# Smart_Light_Panel.net
KiCad netlist of a schematic drawn in EAGLE
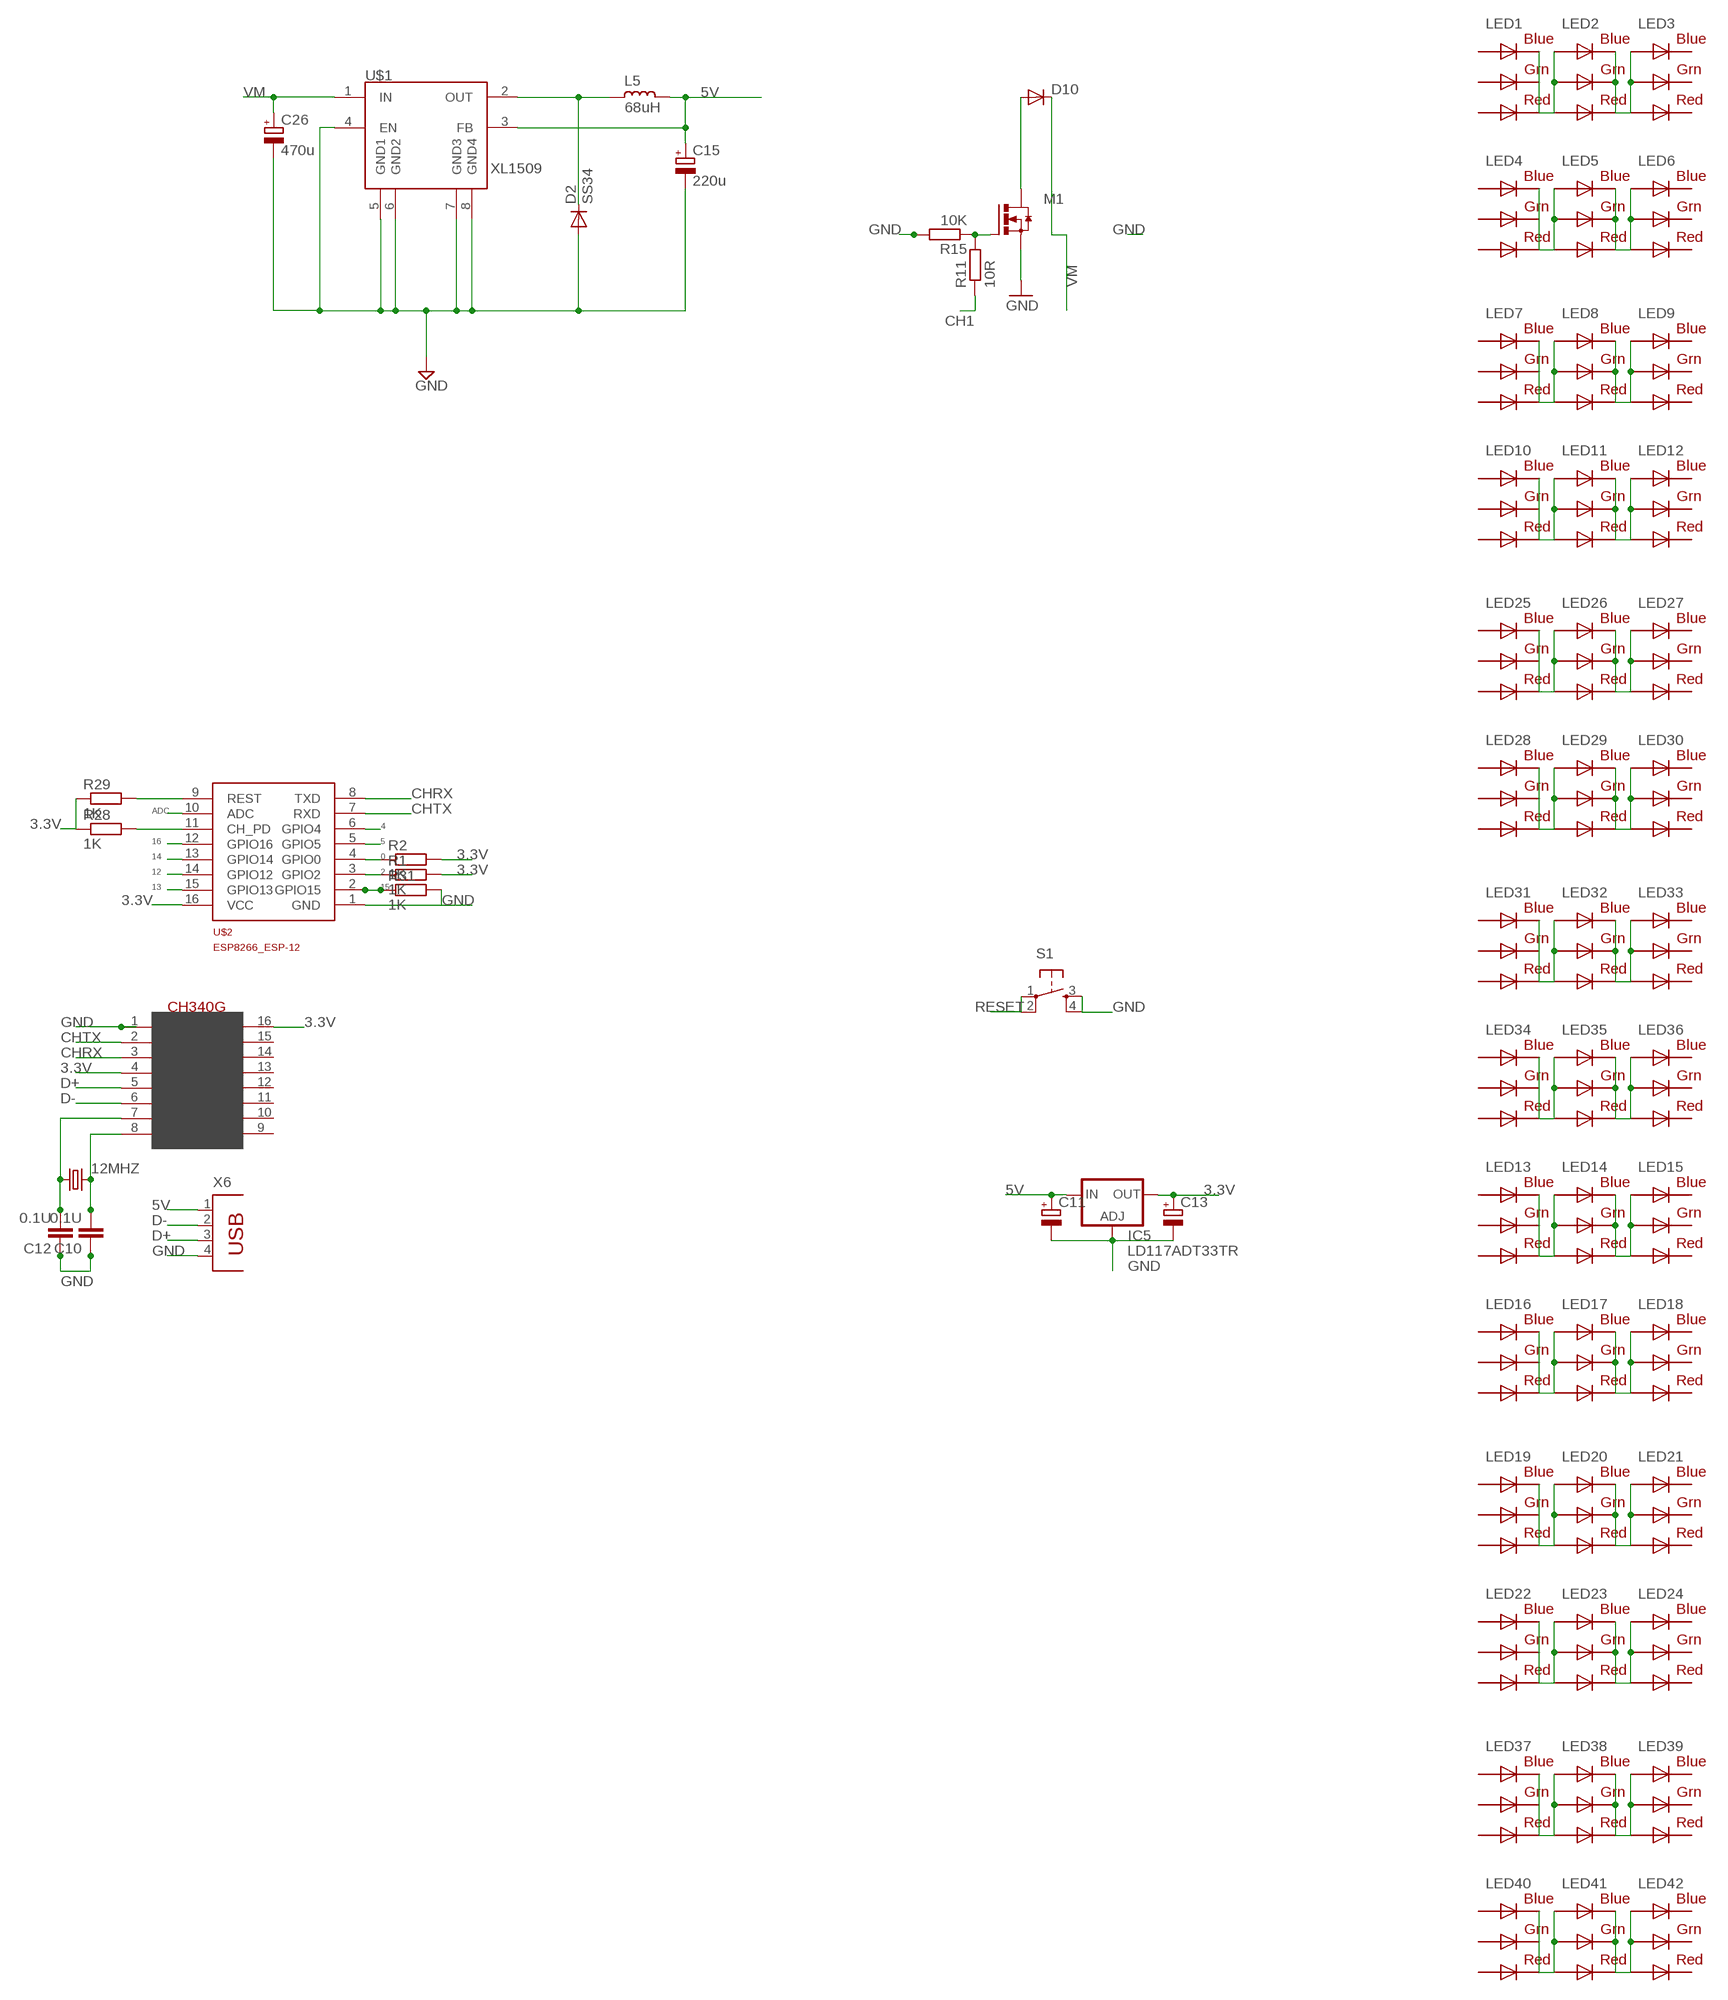
[diagram p0: schematic, sheet 1, part 1 of 2]
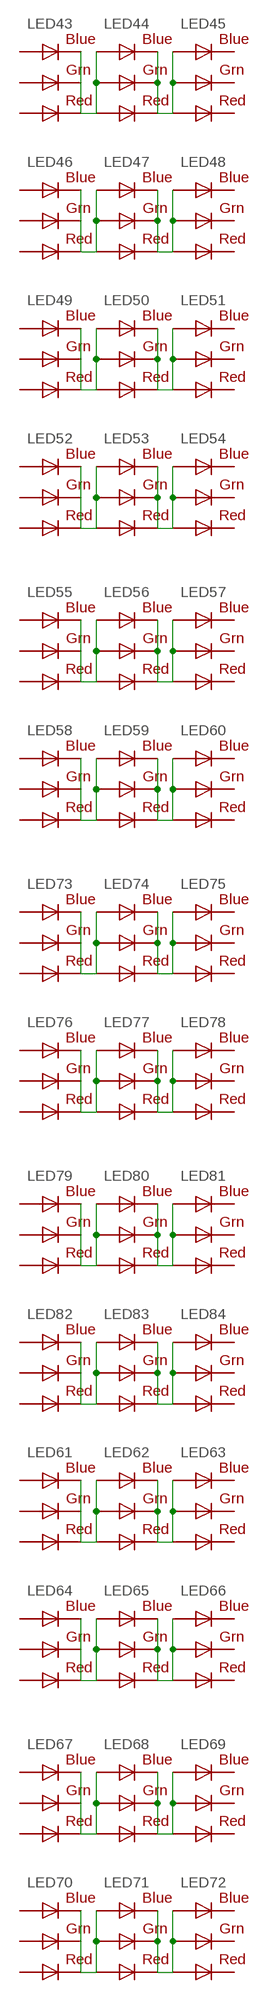
[diagram p1: schematic, sheet 1, part 2 of 2]

(export (version "E")
  (design (tool "Eeschema 10.0.6"))
  (components
    (comp (ref "12MHZ")
      (value "CRYSTALHC49UP")
      (footprint "eagle-import:HC49UP")
      (libsource (lib "eagle-import") (part "CRYSTALHC49UP"))
    )
    (comp (ref "C10")
      (value "0.1U")
      (footprint "eagle-import:C1206")
      (libsource (lib "eagle-import") (part "C-EUC1206"))
    )
    (comp (ref "C11")
      (value "CPOL-EUC")
      (footprint "eagle-import:PANASONIC_C")
      (libsource (lib "eagle-import") (part "CPOL-EUC"))
    )
    (comp (ref "C12")
      (value "0.1U")
      (footprint "eagle-import:C1206")
      (libsource (lib "eagle-import") (part "C-EUC1206"))
    )
    (comp (ref "C13")
      (value "CPOL-EUC")
      (footprint "eagle-import:PANASONIC_C")
      (libsource (lib "eagle-import") (part "CPOL-EUC"))
    )
    (comp (ref "C15")
      (value "220u")
      (footprint "eagle-import:E2,5-7")
      (libsource (lib "eagle-import") (part "CPOL-EUE2.5-7"))
    )
    (comp (ref "C26")
      (value "470u")
      (footprint "eagle-import:E2,5-7")
      (libsource (lib "eagle-import") (part "CPOL-EUE2.5-7"))
    )
    (comp (ref "D2")
      (value "SS34")
      (footprint "eagle-import:DO-214AC")
      (libsource (lib "eagle-import") (part "DIODE-DO-214AC"))
    )
    (comp (ref "D10")
      (value "DIODESMA-ALT")
      (footprint "eagle-import:SMA-DIODE_ALT")
      (libsource (lib "eagle-import") (part "DIODESMA-ALT"))
    )
    (comp (ref "IC5")
      (value "LD117ADT33TR")
      (footprint "eagle-import:DPACK")
      (libsource (lib "eagle-import") (part "LD117A?DT33TR"))
    )
    (comp (ref "L5")
      (value "68uH")
      (footprint "eagle-import:CD75")
      (libsource (lib "eagle-import") (part "L_CD75"))
    )
    (comp (ref "LED1")
      (value "RGBLED5050")
      (footprint "eagle-import:RGBLED5050")
      (libsource (lib "eagle-import") (part "RGBLED5050"))
    )
    (comp (ref "LED2")
      (value "RGBLED5050")
      (footprint "eagle-import:RGBLED5050")
      (libsource (lib "eagle-import") (part "RGBLED5050"))
    )
    (comp (ref "LED3")
      (value "RGBLED5050")
      (footprint "eagle-import:RGBLED5050")
      (libsource (lib "eagle-import") (part "RGBLED5050"))
    )
    (comp (ref "LED4")
      (value "RGBLED5050")
      (footprint "eagle-import:RGBLED5050")
      (libsource (lib "eagle-import") (part "RGBLED5050"))
    )
    (comp (ref "LED5")
      (value "RGBLED5050")
      (footprint "eagle-import:RGBLED5050")
      (libsource (lib "eagle-import") (part "RGBLED5050"))
    )
    (comp (ref "LED6")
      (value "RGBLED5050")
      (footprint "eagle-import:RGBLED5050")
      (libsource (lib "eagle-import") (part "RGBLED5050"))
    )
    (comp (ref "LED7")
      (value "RGBLED5050")
      (footprint "eagle-import:RGBLED5050")
      (libsource (lib "eagle-import") (part "RGBLED5050"))
    )
    (comp (ref "LED8")
      (value "RGBLED5050")
      (footprint "eagle-import:RGBLED5050")
      (libsource (lib "eagle-import") (part "RGBLED5050"))
    )
    (comp (ref "LED9")
      (value "RGBLED5050")
      (footprint "eagle-import:RGBLED5050")
      (libsource (lib "eagle-import") (part "RGBLED5050"))
    )
    (comp (ref "LED10")
      (value "RGBLED5050")
      (footprint "eagle-import:RGBLED5050")
      (libsource (lib "eagle-import") (part "RGBLED5050"))
    )
    (comp (ref "LED11")
      (value "RGBLED5050")
      (footprint "eagle-import:RGBLED5050")
      (libsource (lib "eagle-import") (part "RGBLED5050"))
    )
    (comp (ref "LED12")
      (value "RGBLED5050")
      (footprint "eagle-import:RGBLED5050")
      (libsource (lib "eagle-import") (part "RGBLED5050"))
    )
    (comp (ref "LED13")
      (value "RGBLED5050")
      (footprint "eagle-import:RGBLED5050")
      (libsource (lib "eagle-import") (part "RGBLED5050"))
    )
    (comp (ref "LED14")
      (value "RGBLED5050")
      (footprint "eagle-import:RGBLED5050")
      (libsource (lib "eagle-import") (part "RGBLED5050"))
    )
    (comp (ref "LED15")
      (value "RGBLED5050")
      (footprint "eagle-import:RGBLED5050")
      (libsource (lib "eagle-import") (part "RGBLED5050"))
    )
    (comp (ref "LED16")
      (value "RGBLED5050")
      (footprint "eagle-import:RGBLED5050")
      (libsource (lib "eagle-import") (part "RGBLED5050"))
    )
    (comp (ref "LED17")
      (value "RGBLED5050")
      (footprint "eagle-import:RGBLED5050")
      (libsource (lib "eagle-import") (part "RGBLED5050"))
    )
    (comp (ref "LED18")
      (value "RGBLED5050")
      (footprint "eagle-import:RGBLED5050")
      (libsource (lib "eagle-import") (part "RGBLED5050"))
    )
    (comp (ref "LED19")
      (value "RGBLED5050")
      (footprint "eagle-import:RGBLED5050")
      (libsource (lib "eagle-import") (part "RGBLED5050"))
    )
    (comp (ref "LED20")
      (value "RGBLED5050")
      (footprint "eagle-import:RGBLED5050")
      (libsource (lib "eagle-import") (part "RGBLED5050"))
    )
    (comp (ref "LED21")
      (value "RGBLED5050")
      (footprint "eagle-import:RGBLED5050")
      (libsource (lib "eagle-import") (part "RGBLED5050"))
    )
    (comp (ref "LED22")
      (value "RGBLED5050")
      (footprint "eagle-import:RGBLED5050")
      (libsource (lib "eagle-import") (part "RGBLED5050"))
    )
    (comp (ref "LED23")
      (value "RGBLED5050")
      (footprint "eagle-import:RGBLED5050")
      (libsource (lib "eagle-import") (part "RGBLED5050"))
    )
    (comp (ref "LED24")
      (value "RGBLED5050")
      (footprint "eagle-import:RGBLED5050")
      (libsource (lib "eagle-import") (part "RGBLED5050"))
    )
    (comp (ref "LED25")
      (value "RGBLED5050")
      (footprint "eagle-import:RGBLED5050")
      (libsource (lib "eagle-import") (part "RGBLED5050"))
    )
    (comp (ref "LED26")
      (value "RGBLED5050")
      (footprint "eagle-import:RGBLED5050")
      (libsource (lib "eagle-import") (part "RGBLED5050"))
    )
    (comp (ref "LED27")
      (value "RGBLED5050")
      (footprint "eagle-import:RGBLED5050")
      (libsource (lib "eagle-import") (part "RGBLED5050"))
    )
    (comp (ref "LED28")
      (value "RGBLED5050")
      (footprint "eagle-import:RGBLED5050")
      (libsource (lib "eagle-import") (part "RGBLED5050"))
    )
    (comp (ref "LED29")
      (value "RGBLED5050")
      (footprint "eagle-import:RGBLED5050")
      (libsource (lib "eagle-import") (part "RGBLED5050"))
    )
    (comp (ref "LED30")
      (value "RGBLED5050")
      (footprint "eagle-import:RGBLED5050")
      (libsource (lib "eagle-import") (part "RGBLED5050"))
    )
    (comp (ref "LED31")
      (value "RGBLED5050")
      (footprint "eagle-import:RGBLED5050")
      (libsource (lib "eagle-import") (part "RGBLED5050"))
    )
    (comp (ref "LED32")
      (value "RGBLED5050")
      (footprint "eagle-import:RGBLED5050")
      (libsource (lib "eagle-import") (part "RGBLED5050"))
    )
    (comp (ref "LED33")
      (value "RGBLED5050")
      (footprint "eagle-import:RGBLED5050")
      (libsource (lib "eagle-import") (part "RGBLED5050"))
    )
    (comp (ref "LED34")
      (value "RGBLED5050")
      (footprint "eagle-import:RGBLED5050")
      (libsource (lib "eagle-import") (part "RGBLED5050"))
    )
    (comp (ref "LED35")
      (value "RGBLED5050")
      (footprint "eagle-import:RGBLED5050")
      (libsource (lib "eagle-import") (part "RGBLED5050"))
    )
    (comp (ref "LED36")
      (value "RGBLED5050")
      (footprint "eagle-import:RGBLED5050")
      (libsource (lib "eagle-import") (part "RGBLED5050"))
    )
    (comp (ref "LED37")
      (value "RGBLED5050")
      (footprint "eagle-import:RGBLED5050")
      (libsource (lib "eagle-import") (part "RGBLED5050"))
    )
    (comp (ref "LED38")
      (value "RGBLED5050")
      (footprint "eagle-import:RGBLED5050")
      (libsource (lib "eagle-import") (part "RGBLED5050"))
    )
    (comp (ref "LED39")
      (value "RGBLED5050")
      (footprint "eagle-import:RGBLED5050")
      (libsource (lib "eagle-import") (part "RGBLED5050"))
    )
    (comp (ref "LED40")
      (value "RGBLED5050")
      (footprint "eagle-import:RGBLED5050")
      (libsource (lib "eagle-import") (part "RGBLED5050"))
    )
    (comp (ref "LED41")
      (value "RGBLED5050")
      (footprint "eagle-import:RGBLED5050")
      (libsource (lib "eagle-import") (part "RGBLED5050"))
    )
    (comp (ref "LED42")
      (value "RGBLED5050")
      (footprint "eagle-import:RGBLED5050")
      (libsource (lib "eagle-import") (part "RGBLED5050"))
    )
    (comp (ref "LED43")
      (value "RGBLED5050")
      (footprint "eagle-import:RGBLED5050")
      (libsource (lib "eagle-import") (part "RGBLED5050"))
    )
    (comp (ref "LED44")
      (value "RGBLED5050")
      (footprint "eagle-import:RGBLED5050")
      (libsource (lib "eagle-import") (part "RGBLED5050"))
    )
    (comp (ref "LED45")
      (value "RGBLED5050")
      (footprint "eagle-import:RGBLED5050")
      (libsource (lib "eagle-import") (part "RGBLED5050"))
    )
    (comp (ref "LED46")
      (value "RGBLED5050")
      (footprint "eagle-import:RGBLED5050")
      (libsource (lib "eagle-import") (part "RGBLED5050"))
    )
    (comp (ref "LED47")
      (value "RGBLED5050")
      (footprint "eagle-import:RGBLED5050")
      (libsource (lib "eagle-import") (part "RGBLED5050"))
    )
    (comp (ref "LED48")
      (value "RGBLED5050")
      (footprint "eagle-import:RGBLED5050")
      (libsource (lib "eagle-import") (part "RGBLED5050"))
    )
    (comp (ref "LED49")
      (value "RGBLED5050")
      (footprint "eagle-import:RGBLED5050")
      (libsource (lib "eagle-import") (part "RGBLED5050"))
    )
    (comp (ref "LED50")
      (value "RGBLED5050")
      (footprint "eagle-import:RGBLED5050")
      (libsource (lib "eagle-import") (part "RGBLED5050"))
    )
    (comp (ref "LED51")
      (value "RGBLED5050")
      (footprint "eagle-import:RGBLED5050")
      (libsource (lib "eagle-import") (part "RGBLED5050"))
    )
    (comp (ref "LED52")
      (value "RGBLED5050")
      (footprint "eagle-import:RGBLED5050")
      (libsource (lib "eagle-import") (part "RGBLED5050"))
    )
    (comp (ref "LED53")
      (value "RGBLED5050")
      (footprint "eagle-import:RGBLED5050")
      (libsource (lib "eagle-import") (part "RGBLED5050"))
    )
    (comp (ref "LED54")
      (value "RGBLED5050")
      (footprint "eagle-import:RGBLED5050")
      (libsource (lib "eagle-import") (part "RGBLED5050"))
    )
    (comp (ref "LED55")
      (value "RGBLED5050")
      (footprint "eagle-import:RGBLED5050")
      (libsource (lib "eagle-import") (part "RGBLED5050"))
    )
    (comp (ref "LED56")
      (value "RGBLED5050")
      (footprint "eagle-import:RGBLED5050")
      (libsource (lib "eagle-import") (part "RGBLED5050"))
    )
    (comp (ref "LED57")
      (value "RGBLED5050")
      (footprint "eagle-import:RGBLED5050")
      (libsource (lib "eagle-import") (part "RGBLED5050"))
    )
    (comp (ref "LED58")
      (value "RGBLED5050")
      (footprint "eagle-import:RGBLED5050")
      (libsource (lib "eagle-import") (part "RGBLED5050"))
    )
    (comp (ref "LED59")
      (value "RGBLED5050")
      (footprint "eagle-import:RGBLED5050")
      (libsource (lib "eagle-import") (part "RGBLED5050"))
    )
    (comp (ref "LED60")
      (value "RGBLED5050")
      (footprint "eagle-import:RGBLED5050")
      (libsource (lib "eagle-import") (part "RGBLED5050"))
    )
    (comp (ref "LED61")
      (value "RGBLED5050")
      (footprint "eagle-import:RGBLED5050")
      (libsource (lib "eagle-import") (part "RGBLED5050"))
    )
    (comp (ref "LED62")
      (value "RGBLED5050")
      (footprint "eagle-import:RGBLED5050")
      (libsource (lib "eagle-import") (part "RGBLED5050"))
    )
    (comp (ref "LED63")
      (value "RGBLED5050")
      (footprint "eagle-import:RGBLED5050")
      (libsource (lib "eagle-import") (part "RGBLED5050"))
    )
    (comp (ref "LED64")
      (value "RGBLED5050")
      (footprint "eagle-import:RGBLED5050")
      (libsource (lib "eagle-import") (part "RGBLED5050"))
    )
    (comp (ref "LED65")
      (value "RGBLED5050")
      (footprint "eagle-import:RGBLED5050")
      (libsource (lib "eagle-import") (part "RGBLED5050"))
    )
    (comp (ref "LED66")
      (value "RGBLED5050")
      (footprint "eagle-import:RGBLED5050")
      (libsource (lib "eagle-import") (part "RGBLED5050"))
    )
    (comp (ref "LED67")
      (value "RGBLED5050")
      (footprint "eagle-import:RGBLED5050")
      (libsource (lib "eagle-import") (part "RGBLED5050"))
    )
    (comp (ref "LED68")
      (value "RGBLED5050")
      (footprint "eagle-import:RGBLED5050")
      (libsource (lib "eagle-import") (part "RGBLED5050"))
    )
    (comp (ref "LED69")
      (value "RGBLED5050")
      (footprint "eagle-import:RGBLED5050")
      (libsource (lib "eagle-import") (part "RGBLED5050"))
    )
    (comp (ref "LED70")
      (value "RGBLED5050")
      (footprint "eagle-import:RGBLED5050")
      (libsource (lib "eagle-import") (part "RGBLED5050"))
    )
    (comp (ref "LED71")
      (value "RGBLED5050")
      (footprint "eagle-import:RGBLED5050")
      (libsource (lib "eagle-import") (part "RGBLED5050"))
    )
    (comp (ref "LED72")
      (value "RGBLED5050")
      (footprint "eagle-import:RGBLED5050")
      (libsource (lib "eagle-import") (part "RGBLED5050"))
    )
    (comp (ref "LED73")
      (value "RGBLED5050")
      (footprint "eagle-import:RGBLED5050")
      (libsource (lib "eagle-import") (part "RGBLED5050"))
    )
    (comp (ref "LED74")
      (value "RGBLED5050")
      (footprint "eagle-import:RGBLED5050")
      (libsource (lib "eagle-import") (part "RGBLED5050"))
    )
    (comp (ref "LED75")
      (value "RGBLED5050")
      (footprint "eagle-import:RGBLED5050")
      (libsource (lib "eagle-import") (part "RGBLED5050"))
    )
    (comp (ref "LED76")
      (value "RGBLED5050")
      (footprint "eagle-import:RGBLED5050")
      (libsource (lib "eagle-import") (part "RGBLED5050"))
    )
    (comp (ref "LED77")
      (value "RGBLED5050")
      (footprint "eagle-import:RGBLED5050")
      (libsource (lib "eagle-import") (part "RGBLED5050"))
    )
    (comp (ref "LED78")
      (value "RGBLED5050")
      (footprint "eagle-import:RGBLED5050")
      (libsource (lib "eagle-import") (part "RGBLED5050"))
    )
    (comp (ref "LED79")
      (value "RGBLED5050")
      (footprint "eagle-import:RGBLED5050")
      (libsource (lib "eagle-import") (part "RGBLED5050"))
    )
    (comp (ref "LED80")
      (value "RGBLED5050")
      (footprint "eagle-import:RGBLED5050")
      (libsource (lib "eagle-import") (part "RGBLED5050"))
    )
    (comp (ref "LED81")
      (value "RGBLED5050")
      (footprint "eagle-import:RGBLED5050")
      (libsource (lib "eagle-import") (part "RGBLED5050"))
    )
    (comp (ref "LED82")
      (value "RGBLED5050")
      (footprint "eagle-import:RGBLED5050")
      (libsource (lib "eagle-import") (part "RGBLED5050"))
    )
    (comp (ref "LED83")
      (value "RGBLED5050")
      (footprint "eagle-import:RGBLED5050")
      (libsource (lib "eagle-import") (part "RGBLED5050"))
    )
    (comp (ref "LED84")
      (value "RGBLED5050")
      (footprint "eagle-import:RGBLED5050")
      (libsource (lib "eagle-import") (part "RGBLED5050"))
    )
    (comp (ref "M1")
      (value "IRLR024N")
      (footprint "eagle-import:TO252")
      (libsource (lib "eagle-import") (part "IRLR024N"))
    )
    (comp (ref "R1")
      (value "1K")
      (footprint "eagle-import:M1206")
      (libsource (lib "eagle-import") (part "R-EU_M1206"))
    )
    (comp (ref "R2")
      (value "1K")
      (footprint "eagle-import:M1206")
      (libsource (lib "eagle-import") (part "R-EU_M1206"))
    )
    (comp (ref "R11")
      (value "10R")
      (footprint "eagle-import:M1206")
      (libsource (lib "eagle-import") (part "resistor_R-EU_M1206"))
    )
    (comp (ref "R15")
      (value "10K")
      (footprint "eagle-import:M1206")
      (libsource (lib "eagle-import") (part "resistor_R-EU_M1206"))
    )
    (comp (ref "R28")
      (value "1K")
      (footprint "eagle-import:M1206")
      (libsource (lib "eagle-import") (part "R-EU_M1206"))
    )
    (comp (ref "R29")
      (value "1K")
      (footprint "eagle-import:M1206")
      (libsource (lib "eagle-import") (part "R-EU_M1206"))
    )
    (comp (ref "R31")
      (value "1K")
      (footprint "eagle-import:M1206")
      (libsource (lib "eagle-import") (part "R-EU_M1206"))
    )
    (comp (ref "S1")
      (value "TAC_SWITCHPTH")
      (footprint "eagle-import:TACTILE-PTH")
      (libsource (lib "eagle-import") (part "TAC_SWITCHPTH"))
    )
    (comp (ref "U$1")
      (value "XL1509")
      (footprint "eagle-import:SO08")
      (libsource (lib "eagle-import") (part "XL1509"))
    )
    (comp (ref "U$2")
      (value "ESP8266_ESP-12")
      (footprint "eagle-import:ESP8266-ESP12")
      (libsource (lib "eagle-import") (part "ESP8266_ESP-12"))
    )
    (comp (ref "U$4")
      (value "CH340G")
      (footprint "eagle-import:SOIC16")
      (libsource (lib "eagle-import") (part "CH340G"))
    )
    (comp (ref "X6")
      (value "PN61729")
      (footprint "eagle-import:PN61729")
      (libsource (lib "eagle-import") (part "PN61729"))
    )
  )
  (nets
    (net (code "1") (name "/0") (class "Default")
      (node (ref "R2") (pin "1") (pinfunction "1_1") (pintype "passive"))
      (node (ref "U$2") (pin "4") (pinfunction "GPIO0_4") (pintype "bidirectional"))
    )
    (net (code "2") (name "/2") (class "Default")
      (node (ref "R1") (pin "1") (pinfunction "1_1") (pintype "passive"))
      (node (ref "U$2") (pin "3") (pinfunction "GPIO2_3") (pintype "bidirectional"))
    )
    (net (code "3") (name "/3.3V") (class "Default")
      (node (ref "C13") (pin "+") (pinfunction "+_+") (pintype "passive"))
      (node (ref "IC5") (pin "4") (pinfunction "OUT_4") (pintype "passive"))
      (node (ref "R1") (pin "2") (pinfunction "2_2") (pintype "passive"))
      (node (ref "R2") (pin "2") (pinfunction "2_2") (pintype "passive"))
      (node (ref "R28") (pin "1") (pinfunction "1_1") (pintype "passive"))
      (node (ref "R29") (pin "1") (pinfunction "1_1") (pintype "passive"))
      (node (ref "U$2") (pin "16") (pinfunction "VCC_16") (pintype "bidirectional"))
      (node (ref "U$4") (pin "16") (pinfunction "VCC_16") (pintype "bidirectional"))
      (node (ref "U$4") (pin "4") (pinfunction "V3_4") (pintype "bidirectional"))
    )
    (net (code "4") (name "/4") (class "Default")
      (node (ref "U$2") (pin "6") (pinfunction "GPIO4_6") (pintype "bidirectional"))
    )
    (net (code "5") (name "/5") (class "Default")
      (node (ref "U$2") (pin "5") (pinfunction "GPIO5_5") (pintype "bidirectional"))
    )
    (net (code "6") (name "/5V") (class "Default")
      (node (ref "C11") (pin "+") (pinfunction "+_+") (pintype "passive"))
      (node (ref "C15") (pin "+") (pinfunction "+_+") (pintype "passive"))
      (node (ref "IC5") (pin "3") (pinfunction "IN_3") (pintype "input"))
      (node (ref "L5") (pin "1") (pinfunction "1_1") (pintype "passive"))
      (node (ref "U$1") (pin "3") (pinfunction "FB_3") (pintype "bidirectional"))
      (node (ref "X6") (pin "1") (pinfunction "1_1") (pintype "passive"))
    )
    (net (code "7") (name "/12") (class "Default")
      (node (ref "U$2") (pin "14") (pinfunction "GPIO12_14") (pintype "bidirectional"))
    )
    (net (code "8") (name "/13") (class "Default")
      (node (ref "U$2") (pin "15") (pinfunction "GPIO13_15") (pintype "bidirectional"))
    )
    (net (code "9") (name "/14") (class "Default")
      (node (ref "U$2") (pin "13") (pinfunction "GPIO14_13") (pintype "bidirectional"))
    )
    (net (code "10") (name "/15") (class "Default")
      (node (ref "R31") (pin "1") (pinfunction "1_1") (pintype "passive"))
      (node (ref "U$2") (pin "2") (pinfunction "GPIO15_2") (pintype "bidirectional"))
    )
    (net (code "11") (name "/16") (class "Default")
      (node (ref "U$2") (pin "12") (pinfunction "GPIO16_12") (pintype "bidirectional"))
    )
    (net (code "12") (name "/ADC") (class "Default")
      (node (ref "U$2") (pin "10") (pinfunction "ADC_10") (pintype "bidirectional"))
    )
    (net (code "13") (name "/CH1") (class "Default")
      (node (ref "R11") (pin "1") (pinfunction "1_1") (pintype "passive"))
    )
    (net (code "14") (name "/CHRX") (class "Default")
      (node (ref "U$2") (pin "8") (pinfunction "TXD_8") (pintype "bidirectional"))
      (node (ref "U$4") (pin "3") (pinfunction "RX_3") (pintype "bidirectional"))
    )
    (net (code "15") (name "/CHTX") (class "Default")
      (node (ref "U$2") (pin "7") (pinfunction "RXD_7") (pintype "bidirectional"))
      (node (ref "U$4") (pin "2") (pinfunction "TX_2") (pintype "bidirectional"))
    )
    (net (code "16") (name "/D+") (class "Default")
      (node (ref "U$4") (pin "5") (pinfunction "D+_5") (pintype "bidirectional"))
      (node (ref "X6") (pin "3") (pinfunction "3_3") (pintype "passive"))
    )
    (net (code "17") (name "/D-") (class "Default")
      (node (ref "U$4") (pin "6") (pinfunction "D-_6") (pintype "bidirectional"))
      (node (ref "X6") (pin "2") (pinfunction "2_2") (pintype "passive"))
    )
    (net (code "18") (name "/RESET") (class "Default")
      (node (ref "R29") (pin "2") (pinfunction "2_2") (pintype "passive"))
      (node (ref "S1") (pin "1") (pinfunction "1_1") (pintype "passive"))
      (node (ref "S1") (pin "2") (pinfunction "2_2") (pintype "passive"))
      (node (ref "U$2") (pin "9") (pinfunction "REST_9") (pintype "bidirectional"))
    )
    (net (code "19") (name "/VM") (class "Default")
      (node (ref "C26") (pin "+") (pinfunction "+_+") (pintype "passive"))
      (node (ref "D10") (pin "C") (pinfunction "C_C") (pintype "passive"))
      (node (ref "U$1") (pin "1") (pinfunction "IN_1") (pintype "bidirectional"))
    )
    (net (code "20") (name "GND") (class "Default")
      (node (ref "C10") (pin "1") (pinfunction "1_1") (pintype "passive"))
      (node (ref "C11") (pin "-") (pinfunction "-_-") (pintype "passive"))
      (node (ref "C12") (pin "1") (pinfunction "1_1") (pintype "passive"))
      (node (ref "C13") (pin "-") (pinfunction "-_-") (pintype "passive"))
      (node (ref "C15") (pin "-") (pinfunction "-_-") (pintype "passive"))
      (node (ref "C26") (pin "-") (pinfunction "-_-") (pintype "passive"))
      (node (ref "D2") (pin "2") (pinfunction "A_2") (pintype "passive"))
      (node (ref "IC5") (pin "1") (pinfunction "ADJ_1") (pintype "input"))
      (node (ref "M1") (pin "2") (pinfunction "S_2") (pintype "passive"))
      (node (ref "R15") (pin "2") (pinfunction "2_2") (pintype "passive"))
      (node (ref "R31") (pin "2") (pinfunction "2_2") (pintype "passive"))
      (node (ref "S1") (pin "3") (pinfunction "3_3") (pintype "passive"))
      (node (ref "S1") (pin "4") (pinfunction "4_4") (pintype "passive"))
      (node (ref "U$1") (pin "4") (pinfunction "EN_4") (pintype "bidirectional"))
      (node (ref "U$1") (pin "5") (pinfunction "GND1_5") (pintype "bidirectional"))
      (node (ref "U$1") (pin "6") (pinfunction "GND2_6") (pintype "bidirectional"))
      (node (ref "U$1") (pin "7") (pinfunction "GND3_7") (pintype "bidirectional"))
      (node (ref "U$1") (pin "8") (pinfunction "GND4_8") (pintype "bidirectional"))
      (node (ref "U$2") (pin "1") (pinfunction "GND_1") (pintype "bidirectional"))
      (node (ref "U$4") (pin "1") (pinfunction "GND_1") (pintype "bidirectional"))
      (node (ref "X6") (pin "4") (pinfunction "4_4") (pintype "passive"))
    )
    (net (code "21") (name "Net-(D2-C)") (class "Default")
      (node (ref "D2") (pin "1") (pinfunction "C_1") (pintype "passive"))
      (node (ref "L5") (pin "2") (pinfunction "2_2") (pintype "passive"))
      (node (ref "U$1") (pin "2") (pinfunction "OUT_2") (pintype "bidirectional"))
    )
    (net (code "22") (name "Net-(LED1-BLUE_C)") (class "Default")
      (node (ref "LED1") (pin "4") (pinfunction "BLUE_C_4") (pintype "bidirectional"))
      (node (ref "LED1") (pin "5") (pinfunction "RED_C_5") (pintype "bidirectional"))
      (node (ref "LED1") (pin "6") (pinfunction "GREEN_C_6") (pintype "bidirectional"))
      (node (ref "LED2") (pin "1") (pinfunction "GREEN_A_1") (pintype "bidirectional"))
      (node (ref "LED2") (pin "2") (pinfunction "RED_A_2") (pintype "bidirectional"))
      (node (ref "LED2") (pin "3") (pinfunction "BLUE_A_3") (pintype "bidirectional"))
    )
    (net (code "23") (name "Net-(LED2-BLUE_C)") (class "Default")
      (node (ref "LED2") (pin "4") (pinfunction "BLUE_C_4") (pintype "bidirectional"))
      (node (ref "LED2") (pin "5") (pinfunction "RED_C_5") (pintype "bidirectional"))
      (node (ref "LED2") (pin "6") (pinfunction "GREEN_C_6") (pintype "bidirectional"))
      (node (ref "LED3") (pin "1") (pinfunction "GREEN_A_1") (pintype "bidirectional"))
      (node (ref "LED3") (pin "2") (pinfunction "RED_A_2") (pintype "bidirectional"))
      (node (ref "LED3") (pin "3") (pinfunction "BLUE_A_3") (pintype "bidirectional"))
    )
    (net (code "24") (name "Net-(LED4-BLUE_C)") (class "Default")
      (node (ref "LED4") (pin "4") (pinfunction "BLUE_C_4") (pintype "bidirectional"))
      (node (ref "LED4") (pin "5") (pinfunction "RED_C_5") (pintype "bidirectional"))
      (node (ref "LED4") (pin "6") (pinfunction "GREEN_C_6") (pintype "bidirectional"))
      (node (ref "LED5") (pin "1") (pinfunction "GREEN_A_1") (pintype "bidirectional"))
      (node (ref "LED5") (pin "2") (pinfunction "RED_A_2") (pintype "bidirectional"))
      (node (ref "LED5") (pin "3") (pinfunction "BLUE_A_3") (pintype "bidirectional"))
    )
    (net (code "25") (name "Net-(LED5-BLUE_C)") (class "Default")
      (node (ref "LED5") (pin "4") (pinfunction "BLUE_C_4") (pintype "bidirectional"))
      (node (ref "LED5") (pin "5") (pinfunction "RED_C_5") (pintype "bidirectional"))
      (node (ref "LED5") (pin "6") (pinfunction "GREEN_C_6") (pintype "bidirectional"))
      (node (ref "LED6") (pin "1") (pinfunction "GREEN_A_1") (pintype "bidirectional"))
      (node (ref "LED6") (pin "2") (pinfunction "RED_A_2") (pintype "bidirectional"))
      (node (ref "LED6") (pin "3") (pinfunction "BLUE_A_3") (pintype "bidirectional"))
    )
    (net (code "26") (name "Net-(LED7-BLUE_C)") (class "Default")
      (node (ref "LED7") (pin "4") (pinfunction "BLUE_C_4") (pintype "bidirectional"))
      (node (ref "LED7") (pin "5") (pinfunction "RED_C_5") (pintype "bidirectional"))
      (node (ref "LED7") (pin "6") (pinfunction "GREEN_C_6") (pintype "bidirectional"))
      (node (ref "LED8") (pin "1") (pinfunction "GREEN_A_1") (pintype "bidirectional"))
      (node (ref "LED8") (pin "2") (pinfunction "RED_A_2") (pintype "bidirectional"))
      (node (ref "LED8") (pin "3") (pinfunction "BLUE_A_3") (pintype "bidirectional"))
    )
    (net (code "27") (name "Net-(LED8-BLUE_C)") (class "Default")
      (node (ref "LED8") (pin "4") (pinfunction "BLUE_C_4") (pintype "bidirectional"))
      (node (ref "LED8") (pin "5") (pinfunction "RED_C_5") (pintype "bidirectional"))
      (node (ref "LED8") (pin "6") (pinfunction "GREEN_C_6") (pintype "bidirectional"))
      (node (ref "LED9") (pin "1") (pinfunction "GREEN_A_1") (pintype "bidirectional"))
      (node (ref "LED9") (pin "2") (pinfunction "RED_A_2") (pintype "bidirectional"))
      (node (ref "LED9") (pin "3") (pinfunction "BLUE_A_3") (pintype "bidirectional"))
    )
    (net (code "28") (name "Net-(LED10-BLUE_C)") (class "Default")
      (node (ref "LED10") (pin "4") (pinfunction "BLUE_C_4") (pintype "bidirectional"))
      (node (ref "LED10") (pin "5") (pinfunction "RED_C_5") (pintype "bidirectional"))
      (node (ref "LED10") (pin "6") (pinfunction "GREEN_C_6") (pintype "bidirectional"))
      (node (ref "LED11") (pin "1") (pinfunction "GREEN_A_1") (pintype "bidirectional"))
      (node (ref "LED11") (pin "2") (pinfunction "RED_A_2") (pintype "bidirectional"))
      (node (ref "LED11") (pin "3") (pinfunction "BLUE_A_3") (pintype "bidirectional"))
    )
    (net (code "29") (name "Net-(LED11-BLUE_C)") (class "Default")
      (node (ref "LED11") (pin "4") (pinfunction "BLUE_C_4") (pintype "bidirectional"))
      (node (ref "LED11") (pin "5") (pinfunction "RED_C_5") (pintype "bidirectional"))
      (node (ref "LED11") (pin "6") (pinfunction "GREEN_C_6") (pintype "bidirectional"))
      (node (ref "LED12") (pin "1") (pinfunction "GREEN_A_1") (pintype "bidirectional"))
      (node (ref "LED12") (pin "2") (pinfunction "RED_A_2") (pintype "bidirectional"))
      (node (ref "LED12") (pin "3") (pinfunction "BLUE_A_3") (pintype "bidirectional"))
    )
    (net (code "30") (name "Net-(LED13-BLUE_C)") (class "Default")
      (node (ref "LED13") (pin "4") (pinfunction "BLUE_C_4") (pintype "bidirectional"))
      (node (ref "LED13") (pin "5") (pinfunction "RED_C_5") (pintype "bidirectional"))
      (node (ref "LED13") (pin "6") (pinfunction "GREEN_C_6") (pintype "bidirectional"))
      (node (ref "LED14") (pin "1") (pinfunction "GREEN_A_1") (pintype "bidirectional"))
      (node (ref "LED14") (pin "2") (pinfunction "RED_A_2") (pintype "bidirectional"))
      (node (ref "LED14") (pin "3") (pinfunction "BLUE_A_3") (pintype "bidirectional"))
    )
    (net (code "31") (name "Net-(LED14-BLUE_C)") (class "Default")
      (node (ref "LED14") (pin "4") (pinfunction "BLUE_C_4") (pintype "bidirectional"))
      (node (ref "LED14") (pin "5") (pinfunction "RED_C_5") (pintype "bidirectional"))
      (node (ref "LED14") (pin "6") (pinfunction "GREEN_C_6") (pintype "bidirectional"))
      (node (ref "LED15") (pin "1") (pinfunction "GREEN_A_1") (pintype "bidirectional"))
      (node (ref "LED15") (pin "2") (pinfunction "RED_A_2") (pintype "bidirectional"))
      (node (ref "LED15") (pin "3") (pinfunction "BLUE_A_3") (pintype "bidirectional"))
    )
    (net (code "32") (name "Net-(LED16-BLUE_C)") (class "Default")
      (node (ref "LED16") (pin "4") (pinfunction "BLUE_C_4") (pintype "bidirectional"))
      (node (ref "LED16") (pin "5") (pinfunction "RED_C_5") (pintype "bidirectional"))
      (node (ref "LED16") (pin "6") (pinfunction "GREEN_C_6") (pintype "bidirectional"))
      (node (ref "LED17") (pin "1") (pinfunction "GREEN_A_1") (pintype "bidirectional"))
      (node (ref "LED17") (pin "2") (pinfunction "RED_A_2") (pintype "bidirectional"))
      (node (ref "LED17") (pin "3") (pinfunction "BLUE_A_3") (pintype "bidirectional"))
    )
    (net (code "33") (name "Net-(LED17-BLUE_C)") (class "Default")
      (node (ref "LED17") (pin "4") (pinfunction "BLUE_C_4") (pintype "bidirectional"))
      (node (ref "LED17") (pin "5") (pinfunction "RED_C_5") (pintype "bidirectional"))
      (node (ref "LED17") (pin "6") (pinfunction "GREEN_C_6") (pintype "bidirectional"))
      (node (ref "LED18") (pin "1") (pinfunction "GREEN_A_1") (pintype "bidirectional"))
      (node (ref "LED18") (pin "2") (pinfunction "RED_A_2") (pintype "bidirectional"))
      (node (ref "LED18") (pin "3") (pinfunction "BLUE_A_3") (pintype "bidirectional"))
    )
    (net (code "34") (name "Net-(LED19-BLUE_C)") (class "Default")
      (node (ref "LED19") (pin "4") (pinfunction "BLUE_C_4") (pintype "bidirectional"))
      (node (ref "LED19") (pin "5") (pinfunction "RED_C_5") (pintype "bidirectional"))
      (node (ref "LED19") (pin "6") (pinfunction "GREEN_C_6") (pintype "bidirectional"))
      (node (ref "LED20") (pin "1") (pinfunction "GREEN_A_1") (pintype "bidirectional"))
      (node (ref "LED20") (pin "2") (pinfunction "RED_A_2") (pintype "bidirectional"))
      (node (ref "LED20") (pin "3") (pinfunction "BLUE_A_3") (pintype "bidirectional"))
    )
    (net (code "35") (name "Net-(LED20-BLUE_C)") (class "Default")
      (node (ref "LED20") (pin "4") (pinfunction "BLUE_C_4") (pintype "bidirectional"))
      (node (ref "LED20") (pin "5") (pinfunction "RED_C_5") (pintype "bidirectional"))
      (node (ref "LED20") (pin "6") (pinfunction "GREEN_C_6") (pintype "bidirectional"))
      (node (ref "LED21") (pin "1") (pinfunction "GREEN_A_1") (pintype "bidirectional"))
      (node (ref "LED21") (pin "2") (pinfunction "RED_A_2") (pintype "bidirectional"))
      (node (ref "LED21") (pin "3") (pinfunction "BLUE_A_3") (pintype "bidirectional"))
    )
    (net (code "36") (name "Net-(LED22-BLUE_C)") (class "Default")
      (node (ref "LED22") (pin "4") (pinfunction "BLUE_C_4") (pintype "bidirectional"))
      (node (ref "LED22") (pin "5") (pinfunction "RED_C_5") (pintype "bidirectional"))
      (node (ref "LED22") (pin "6") (pinfunction "GREEN_C_6") (pintype "bidirectional"))
      (node (ref "LED23") (pin "1") (pinfunction "GREEN_A_1") (pintype "bidirectional"))
      (node (ref "LED23") (pin "2") (pinfunction "RED_A_2") (pintype "bidirectional"))
      (node (ref "LED23") (pin "3") (pinfunction "BLUE_A_3") (pintype "bidirectional"))
    )
    (net (code "37") (name "Net-(LED23-BLUE_C)") (class "Default")
      (node (ref "LED23") (pin "4") (pinfunction "BLUE_C_4") (pintype "bidirectional"))
      (node (ref "LED23") (pin "5") (pinfunction "RED_C_5") (pintype "bidirectional"))
      (node (ref "LED23") (pin "6") (pinfunction "GREEN_C_6") (pintype "bidirectional"))
      (node (ref "LED24") (pin "1") (pinfunction "GREEN_A_1") (pintype "bidirectional"))
      (node (ref "LED24") (pin "2") (pinfunction "RED_A_2") (pintype "bidirectional"))
      (node (ref "LED24") (pin "3") (pinfunction "BLUE_A_3") (pintype "bidirectional"))
    )
    (net (code "38") (name "Net-(LED25-BLUE_C)") (class "Default")
      (node (ref "LED25") (pin "4") (pinfunction "BLUE_C_4") (pintype "bidirectional"))
      (node (ref "LED25") (pin "5") (pinfunction "RED_C_5") (pintype "bidirectional"))
      (node (ref "LED25") (pin "6") (pinfunction "GREEN_C_6") (pintype "bidirectional"))
      (node (ref "LED26") (pin "1") (pinfunction "GREEN_A_1") (pintype "bidirectional"))
      (node (ref "LED26") (pin "2") (pinfunction "RED_A_2") (pintype "bidirectional"))
      (node (ref "LED26") (pin "3") (pinfunction "BLUE_A_3") (pintype "bidirectional"))
    )
    (net (code "39") (name "Net-(LED26-BLUE_C)") (class "Default")
      (node (ref "LED26") (pin "4") (pinfunction "BLUE_C_4") (pintype "bidirectional"))
      (node (ref "LED26") (pin "5") (pinfunction "RED_C_5") (pintype "bidirectional"))
      (node (ref "LED26") (pin "6") (pinfunction "GREEN_C_6") (pintype "bidirectional"))
      (node (ref "LED27") (pin "1") (pinfunction "GREEN_A_1") (pintype "bidirectional"))
      (node (ref "LED27") (pin "2") (pinfunction "RED_A_2") (pintype "bidirectional"))
      (node (ref "LED27") (pin "3") (pinfunction "BLUE_A_3") (pintype "bidirectional"))
    )
    (net (code "40") (name "Net-(LED28-BLUE_C)") (class "Default")
      (node (ref "LED28") (pin "4") (pinfunction "BLUE_C_4") (pintype "bidirectional"))
      (node (ref "LED28") (pin "5") (pinfunction "RED_C_5") (pintype "bidirectional"))
      (node (ref "LED28") (pin "6") (pinfunction "GREEN_C_6") (pintype "bidirectional"))
      (node (ref "LED29") (pin "1") (pinfunction "GREEN_A_1") (pintype "bidirectional"))
      (node (ref "LED29") (pin "2") (pinfunction "RED_A_2") (pintype "bidirectional"))
      (node (ref "LED29") (pin "3") (pinfunction "BLUE_A_3") (pintype "bidirectional"))
    )
    (net (code "41") (name "Net-(LED29-BLUE_C)") (class "Default")
      (node (ref "LED29") (pin "4") (pinfunction "BLUE_C_4") (pintype "bidirectional"))
      (node (ref "LED29") (pin "5") (pinfunction "RED_C_5") (pintype "bidirectional"))
      (node (ref "LED29") (pin "6") (pinfunction "GREEN_C_6") (pintype "bidirectional"))
      (node (ref "LED30") (pin "1") (pinfunction "GREEN_A_1") (pintype "bidirectional"))
      (node (ref "LED30") (pin "2") (pinfunction "RED_A_2") (pintype "bidirectional"))
      (node (ref "LED30") (pin "3") (pinfunction "BLUE_A_3") (pintype "bidirectional"))
    )
    (net (code "42") (name "Net-(LED31-BLUE_C)") (class "Default")
      (node (ref "LED31") (pin "4") (pinfunction "BLUE_C_4") (pintype "bidirectional"))
      (node (ref "LED31") (pin "5") (pinfunction "RED_C_5") (pintype "bidirectional"))
      (node (ref "LED31") (pin "6") (pinfunction "GREEN_C_6") (pintype "bidirectional"))
      (node (ref "LED32") (pin "1") (pinfunction "GREEN_A_1") (pintype "bidirectional"))
      (node (ref "LED32") (pin "2") (pinfunction "RED_A_2") (pintype "bidirectional"))
      (node (ref "LED32") (pin "3") (pinfunction "BLUE_A_3") (pintype "bidirectional"))
    )
    (net (code "43") (name "Net-(LED32-BLUE_C)") (class "Default")
      (node (ref "LED32") (pin "4") (pinfunction "BLUE_C_4") (pintype "bidirectional"))
      (node (ref "LED32") (pin "5") (pinfunction "RED_C_5") (pintype "bidirectional"))
      (node (ref "LED32") (pin "6") (pinfunction "GREEN_C_6") (pintype "bidirectional"))
      (node (ref "LED33") (pin "1") (pinfunction "GREEN_A_1") (pintype "bidirectional"))
      (node (ref "LED33") (pin "2") (pinfunction "RED_A_2") (pintype "bidirectional"))
      (node (ref "LED33") (pin "3") (pinfunction "BLUE_A_3") (pintype "bidirectional"))
    )
    (net (code "44") (name "Net-(LED34-BLUE_C)") (class "Default")
      (node (ref "LED34") (pin "4") (pinfunction "BLUE_C_4") (pintype "bidirectional"))
      (node (ref "LED34") (pin "5") (pinfunction "RED_C_5") (pintype "bidirectional"))
      (node (ref "LED34") (pin "6") (pinfunction "GREEN_C_6") (pintype "bidirectional"))
      (node (ref "LED35") (pin "1") (pinfunction "GREEN_A_1") (pintype "bidirectional"))
      (node (ref "LED35") (pin "2") (pinfunction "RED_A_2") (pintype "bidirectional"))
      (node (ref "LED35") (pin "3") (pinfunction "BLUE_A_3") (pintype "bidirectional"))
    )
    (net (code "45") (name "Net-(LED35-BLUE_C)") (class "Default")
      (node (ref "LED35") (pin "4") (pinfunction "BLUE_C_4") (pintype "bidirectional"))
      (node (ref "LED35") (pin "5") (pinfunction "RED_C_5") (pintype "bidirectional"))
      (node (ref "LED35") (pin "6") (pinfunction "GREEN_C_6") (pintype "bidirectional"))
      (node (ref "LED36") (pin "1") (pinfunction "GREEN_A_1") (pintype "bidirectional"))
      (node (ref "LED36") (pin "2") (pinfunction "RED_A_2") (pintype "bidirectional"))
      (node (ref "LED36") (pin "3") (pinfunction "BLUE_A_3") (pintype "bidirectional"))
    )
    (net (code "46") (name "Net-(LED37-BLUE_C)") (class "Default")
      (node (ref "LED37") (pin "4") (pinfunction "BLUE_C_4") (pintype "bidirectional"))
      (node (ref "LED37") (pin "5") (pinfunction "RED_C_5") (pintype "bidirectional"))
      (node (ref "LED37") (pin "6") (pinfunction "GREEN_C_6") (pintype "bidirectional"))
      (node (ref "LED38") (pin "1") (pinfunction "GREEN_A_1") (pintype "bidirectional"))
      (node (ref "LED38") (pin "2") (pinfunction "RED_A_2") (pintype "bidirectional"))
      (node (ref "LED38") (pin "3") (pinfunction "BLUE_A_3") (pintype "bidirectional"))
    )
    (net (code "47") (name "Net-(LED38-BLUE_C)") (class "Default")
      (node (ref "LED38") (pin "4") (pinfunction "BLUE_C_4") (pintype "bidirectional"))
      (node (ref "LED38") (pin "5") (pinfunction "RED_C_5") (pintype "bidirectional"))
      (node (ref "LED38") (pin "6") (pinfunction "GREEN_C_6") (pintype "bidirectional"))
      (node (ref "LED39") (pin "1") (pinfunction "GREEN_A_1") (pintype "bidirectional"))
      (node (ref "LED39") (pin "2") (pinfunction "RED_A_2") (pintype "bidirectional"))
      (node (ref "LED39") (pin "3") (pinfunction "BLUE_A_3") (pintype "bidirectional"))
    )
    (net (code "48") (name "Net-(LED40-BLUE_C)") (class "Default")
      (node (ref "LED40") (pin "4") (pinfunction "BLUE_C_4") (pintype "bidirectional"))
      (node (ref "LED40") (pin "5") (pinfunction "RED_C_5") (pintype "bidirectional"))
      (node (ref "LED40") (pin "6") (pinfunction "GREEN_C_6") (pintype "bidirectional"))
      (node (ref "LED41") (pin "1") (pinfunction "GREEN_A_1") (pintype "bidirectional"))
      (node (ref "LED41") (pin "2") (pinfunction "RED_A_2") (pintype "bidirectional"))
      (node (ref "LED41") (pin "3") (pinfunction "BLUE_A_3") (pintype "bidirectional"))
    )
    (net (code "49") (name "Net-(LED41-BLUE_C)") (class "Default")
      (node (ref "LED41") (pin "4") (pinfunction "BLUE_C_4") (pintype "bidirectional"))
      (node (ref "LED41") (pin "5") (pinfunction "RED_C_5") (pintype "bidirectional"))
      (node (ref "LED41") (pin "6") (pinfunction "GREEN_C_6") (pintype "bidirectional"))
      (node (ref "LED42") (pin "1") (pinfunction "GREEN_A_1") (pintype "bidirectional"))
      (node (ref "LED42") (pin "2") (pinfunction "RED_A_2") (pintype "bidirectional"))
      (node (ref "LED42") (pin "3") (pinfunction "BLUE_A_3") (pintype "bidirectional"))
    )
    (net (code "50") (name "Net-(LED43-BLUE_C)") (class "Default")
      (node (ref "LED43") (pin "4") (pinfunction "BLUE_C_4") (pintype "bidirectional"))
      (node (ref "LED43") (pin "5") (pinfunction "RED_C_5") (pintype "bidirectional"))
      (node (ref "LED43") (pin "6") (pinfunction "GREEN_C_6") (pintype "bidirectional"))
      (node (ref "LED44") (pin "1") (pinfunction "GREEN_A_1") (pintype "bidirectional"))
      (node (ref "LED44") (pin "2") (pinfunction "RED_A_2") (pintype "bidirectional"))
      (node (ref "LED44") (pin "3") (pinfunction "BLUE_A_3") (pintype "bidirectional"))
    )
    (net (code "51") (name "Net-(LED44-BLUE_C)") (class "Default")
      (node (ref "LED44") (pin "4") (pinfunction "BLUE_C_4") (pintype "bidirectional"))
      (node (ref "LED44") (pin "5") (pinfunction "RED_C_5") (pintype "bidirectional"))
      (node (ref "LED44") (pin "6") (pinfunction "GREEN_C_6") (pintype "bidirectional"))
      (node (ref "LED45") (pin "1") (pinfunction "GREEN_A_1") (pintype "bidirectional"))
      (node (ref "LED45") (pin "2") (pinfunction "RED_A_2") (pintype "bidirectional"))
      (node (ref "LED45") (pin "3") (pinfunction "BLUE_A_3") (pintype "bidirectional"))
    )
    (net (code "52") (name "Net-(LED46-BLUE_C)") (class "Default")
      (node (ref "LED46") (pin "4") (pinfunction "BLUE_C_4") (pintype "bidirectional"))
      (node (ref "LED46") (pin "5") (pinfunction "RED_C_5") (pintype "bidirectional"))
      (node (ref "LED46") (pin "6") (pinfunction "GREEN_C_6") (pintype "bidirectional"))
      (node (ref "LED47") (pin "1") (pinfunction "GREEN_A_1") (pintype "bidirectional"))
      (node (ref "LED47") (pin "2") (pinfunction "RED_A_2") (pintype "bidirectional"))
      (node (ref "LED47") (pin "3") (pinfunction "BLUE_A_3") (pintype "bidirectional"))
    )
    (net (code "53") (name "Net-(LED47-BLUE_C)") (class "Default")
      (node (ref "LED47") (pin "4") (pinfunction "BLUE_C_4") (pintype "bidirectional"))
      (node (ref "LED47") (pin "5") (pinfunction "RED_C_5") (pintype "bidirectional"))
      (node (ref "LED47") (pin "6") (pinfunction "GREEN_C_6") (pintype "bidirectional"))
      (node (ref "LED48") (pin "1") (pinfunction "GREEN_A_1") (pintype "bidirectional"))
      (node (ref "LED48") (pin "2") (pinfunction "RED_A_2") (pintype "bidirectional"))
      (node (ref "LED48") (pin "3") (pinfunction "BLUE_A_3") (pintype "bidirectional"))
    )
    (net (code "54") (name "Net-(LED49-BLUE_C)") (class "Default")
      (node (ref "LED49") (pin "4") (pinfunction "BLUE_C_4") (pintype "bidirectional"))
      (node (ref "LED49") (pin "5") (pinfunction "RED_C_5") (pintype "bidirectional"))
      (node (ref "LED49") (pin "6") (pinfunction "GREEN_C_6") (pintype "bidirectional"))
      (node (ref "LED50") (pin "1") (pinfunction "GREEN_A_1") (pintype "bidirectional"))
      (node (ref "LED50") (pin "2") (pinfunction "RED_A_2") (pintype "bidirectional"))
      (node (ref "LED50") (pin "3") (pinfunction "BLUE_A_3") (pintype "bidirectional"))
    )
    (net (code "55") (name "Net-(LED50-BLUE_C)") (class "Default")
      (node (ref "LED50") (pin "4") (pinfunction "BLUE_C_4") (pintype "bidirectional"))
      (node (ref "LED50") (pin "5") (pinfunction "RED_C_5") (pintype "bidirectional"))
      (node (ref "LED50") (pin "6") (pinfunction "GREEN_C_6") (pintype "bidirectional"))
      (node (ref "LED51") (pin "1") (pinfunction "GREEN_A_1") (pintype "bidirectional"))
      (node (ref "LED51") (pin "2") (pinfunction "RED_A_2") (pintype "bidirectional"))
      (node (ref "LED51") (pin "3") (pinfunction "BLUE_A_3") (pintype "bidirectional"))
    )
    (net (code "56") (name "Net-(LED52-BLUE_C)") (class "Default")
      (node (ref "LED52") (pin "4") (pinfunction "BLUE_C_4") (pintype "bidirectional"))
      (node (ref "LED52") (pin "5") (pinfunction "RED_C_5") (pintype "bidirectional"))
      (node (ref "LED52") (pin "6") (pinfunction "GREEN_C_6") (pintype "bidirectional"))
      (node (ref "LED53") (pin "1") (pinfunction "GREEN_A_1") (pintype "bidirectional"))
      (node (ref "LED53") (pin "2") (pinfunction "RED_A_2") (pintype "bidirectional"))
      (node (ref "LED53") (pin "3") (pinfunction "BLUE_A_3") (pintype "bidirectional"))
    )
    (net (code "57") (name "Net-(LED53-BLUE_C)") (class "Default")
      (node (ref "LED53") (pin "4") (pinfunction "BLUE_C_4") (pintype "bidirectional"))
      (node (ref "LED53") (pin "5") (pinfunction "RED_C_5") (pintype "bidirectional"))
      (node (ref "LED53") (pin "6") (pinfunction "GREEN_C_6") (pintype "bidirectional"))
      (node (ref "LED54") (pin "1") (pinfunction "GREEN_A_1") (pintype "bidirectional"))
      (node (ref "LED54") (pin "2") (pinfunction "RED_A_2") (pintype "bidirectional"))
      (node (ref "LED54") (pin "3") (pinfunction "BLUE_A_3") (pintype "bidirectional"))
    )
    (net (code "58") (name "Net-(LED55-BLUE_C)") (class "Default")
      (node (ref "LED55") (pin "4") (pinfunction "BLUE_C_4") (pintype "bidirectional"))
      (node (ref "LED55") (pin "5") (pinfunction "RED_C_5") (pintype "bidirectional"))
      (node (ref "LED55") (pin "6") (pinfunction "GREEN_C_6") (pintype "bidirectional"))
      (node (ref "LED56") (pin "1") (pinfunction "GREEN_A_1") (pintype "bidirectional"))
      (node (ref "LED56") (pin "2") (pinfunction "RED_A_2") (pintype "bidirectional"))
      (node (ref "LED56") (pin "3") (pinfunction "BLUE_A_3") (pintype "bidirectional"))
    )
    (net (code "59") (name "Net-(LED56-BLUE_C)") (class "Default")
      (node (ref "LED56") (pin "4") (pinfunction "BLUE_C_4") (pintype "bidirectional"))
      (node (ref "LED56") (pin "5") (pinfunction "RED_C_5") (pintype "bidirectional"))
      (node (ref "LED56") (pin "6") (pinfunction "GREEN_C_6") (pintype "bidirectional"))
      (node (ref "LED57") (pin "1") (pinfunction "GREEN_A_1") (pintype "bidirectional"))
      (node (ref "LED57") (pin "2") (pinfunction "RED_A_2") (pintype "bidirectional"))
      (node (ref "LED57") (pin "3") (pinfunction "BLUE_A_3") (pintype "bidirectional"))
    )
    (net (code "60") (name "Net-(LED58-BLUE_C)") (class "Default")
      (node (ref "LED58") (pin "4") (pinfunction "BLUE_C_4") (pintype "bidirectional"))
      (node (ref "LED58") (pin "5") (pinfunction "RED_C_5") (pintype "bidirectional"))
      (node (ref "LED58") (pin "6") (pinfunction "GREEN_C_6") (pintype "bidirectional"))
      (node (ref "LED59") (pin "1") (pinfunction "GREEN_A_1") (pintype "bidirectional"))
      (node (ref "LED59") (pin "2") (pinfunction "RED_A_2") (pintype "bidirectional"))
      (node (ref "LED59") (pin "3") (pinfunction "BLUE_A_3") (pintype "bidirectional"))
    )
    (net (code "61") (name "Net-(LED59-BLUE_C)") (class "Default")
      (node (ref "LED59") (pin "4") (pinfunction "BLUE_C_4") (pintype "bidirectional"))
      (node (ref "LED59") (pin "5") (pinfunction "RED_C_5") (pintype "bidirectional"))
      (node (ref "LED59") (pin "6") (pinfunction "GREEN_C_6") (pintype "bidirectional"))
      (node (ref "LED60") (pin "1") (pinfunction "GREEN_A_1") (pintype "bidirectional"))
      (node (ref "LED60") (pin "2") (pinfunction "RED_A_2") (pintype "bidirectional"))
      (node (ref "LED60") (pin "3") (pinfunction "BLUE_A_3") (pintype "bidirectional"))
    )
    (net (code "62") (name "Net-(LED61-BLUE_C)") (class "Default")
      (node (ref "LED61") (pin "4") (pinfunction "BLUE_C_4") (pintype "bidirectional"))
      (node (ref "LED61") (pin "5") (pinfunction "RED_C_5") (pintype "bidirectional"))
      (node (ref "LED61") (pin "6") (pinfunction "GREEN_C_6") (pintype "bidirectional"))
      (node (ref "LED62") (pin "1") (pinfunction "GREEN_A_1") (pintype "bidirectional"))
      (node (ref "LED62") (pin "2") (pinfunction "RED_A_2") (pintype "bidirectional"))
      (node (ref "LED62") (pin "3") (pinfunction "BLUE_A_3") (pintype "bidirectional"))
    )
    (net (code "63") (name "Net-(LED62-BLUE_C)") (class "Default")
      (node (ref "LED62") (pin "4") (pinfunction "BLUE_C_4") (pintype "bidirectional"))
      (node (ref "LED62") (pin "5") (pinfunction "RED_C_5") (pintype "bidirectional"))
      (node (ref "LED62") (pin "6") (pinfunction "GREEN_C_6") (pintype "bidirectional"))
      (node (ref "LED63") (pin "1") (pinfunction "GREEN_A_1") (pintype "bidirectional"))
      (node (ref "LED63") (pin "2") (pinfunction "RED_A_2") (pintype "bidirectional"))
      (node (ref "LED63") (pin "3") (pinfunction "BLUE_A_3") (pintype "bidirectional"))
    )
    (net (code "64") (name "Net-(LED64-BLUE_C)") (class "Default")
      (node (ref "LED64") (pin "4") (pinfunction "BLUE_C_4") (pintype "bidirectional"))
      (node (ref "LED64") (pin "5") (pinfunction "RED_C_5") (pintype "bidirectional"))
      (node (ref "LED64") (pin "6") (pinfunction "GREEN_C_6") (pintype "bidirectional"))
      (node (ref "LED65") (pin "1") (pinfunction "GREEN_A_1") (pintype "bidirectional"))
      (node (ref "LED65") (pin "2") (pinfunction "RED_A_2") (pintype "bidirectional"))
      (node (ref "LED65") (pin "3") (pinfunction "BLUE_A_3") (pintype "bidirectional"))
    )
    (net (code "65") (name "Net-(LED65-BLUE_C)") (class "Default")
      (node (ref "LED65") (pin "4") (pinfunction "BLUE_C_4") (pintype "bidirectional"))
      (node (ref "LED65") (pin "5") (pinfunction "RED_C_5") (pintype "bidirectional"))
      (node (ref "LED65") (pin "6") (pinfunction "GREEN_C_6") (pintype "bidirectional"))
      (node (ref "LED66") (pin "1") (pinfunction "GREEN_A_1") (pintype "bidirectional"))
      (node (ref "LED66") (pin "2") (pinfunction "RED_A_2") (pintype "bidirectional"))
      (node (ref "LED66") (pin "3") (pinfunction "BLUE_A_3") (pintype "bidirectional"))
    )
    (net (code "66") (name "Net-(LED67-BLUE_C)") (class "Default")
      (node (ref "LED67") (pin "4") (pinfunction "BLUE_C_4") (pintype "bidirectional"))
      (node (ref "LED67") (pin "5") (pinfunction "RED_C_5") (pintype "bidirectional"))
      (node (ref "LED67") (pin "6") (pinfunction "GREEN_C_6") (pintype "bidirectional"))
      (node (ref "LED68") (pin "1") (pinfunction "GREEN_A_1") (pintype "bidirectional"))
      (node (ref "LED68") (pin "2") (pinfunction "RED_A_2") (pintype "bidirectional"))
      (node (ref "LED68") (pin "3") (pinfunction "BLUE_A_3") (pintype "bidirectional"))
    )
    (net (code "67") (name "Net-(LED68-BLUE_C)") (class "Default")
      (node (ref "LED68") (pin "4") (pinfunction "BLUE_C_4") (pintype "bidirectional"))
      (node (ref "LED68") (pin "5") (pinfunction "RED_C_5") (pintype "bidirectional"))
      (node (ref "LED68") (pin "6") (pinfunction "GREEN_C_6") (pintype "bidirectional"))
      (node (ref "LED69") (pin "1") (pinfunction "GREEN_A_1") (pintype "bidirectional"))
      (node (ref "LED69") (pin "2") (pinfunction "RED_A_2") (pintype "bidirectional"))
      (node (ref "LED69") (pin "3") (pinfunction "BLUE_A_3") (pintype "bidirectional"))
    )
    (net (code "68") (name "Net-(LED70-BLUE_C)") (class "Default")
      (node (ref "LED70") (pin "4") (pinfunction "BLUE_C_4") (pintype "bidirectional"))
      (node (ref "LED70") (pin "5") (pinfunction "RED_C_5") (pintype "bidirectional"))
      (node (ref "LED70") (pin "6") (pinfunction "GREEN_C_6") (pintype "bidirectional"))
      (node (ref "LED71") (pin "1") (pinfunction "GREEN_A_1") (pintype "bidirectional"))
      (node (ref "LED71") (pin "2") (pinfunction "RED_A_2") (pintype "bidirectional"))
      (node (ref "LED71") (pin "3") (pinfunction "BLUE_A_3") (pintype "bidirectional"))
    )
    (net (code "69") (name "Net-(LED71-BLUE_C)") (class "Default")
      (node (ref "LED71") (pin "4") (pinfunction "BLUE_C_4") (pintype "bidirectional"))
      (node (ref "LED71") (pin "5") (pinfunction "RED_C_5") (pintype "bidirectional"))
      (node (ref "LED71") (pin "6") (pinfunction "GREEN_C_6") (pintype "bidirectional"))
      (node (ref "LED72") (pin "1") (pinfunction "GREEN_A_1") (pintype "bidirectional"))
      (node (ref "LED72") (pin "2") (pinfunction "RED_A_2") (pintype "bidirectional"))
      (node (ref "LED72") (pin "3") (pinfunction "BLUE_A_3") (pintype "bidirectional"))
    )
    (net (code "70") (name "Net-(LED73-BLUE_C)") (class "Default")
      (node (ref "LED73") (pin "4") (pinfunction "BLUE_C_4") (pintype "bidirectional"))
      (node (ref "LED73") (pin "5") (pinfunction "RED_C_5") (pintype "bidirectional"))
      (node (ref "LED73") (pin "6") (pinfunction "GREEN_C_6") (pintype "bidirectional"))
      (node (ref "LED74") (pin "1") (pinfunction "GREEN_A_1") (pintype "bidirectional"))
      (node (ref "LED74") (pin "2") (pinfunction "RED_A_2") (pintype "bidirectional"))
      (node (ref "LED74") (pin "3") (pinfunction "BLUE_A_3") (pintype "bidirectional"))
    )
    (net (code "71") (name "Net-(LED74-BLUE_C)") (class "Default")
      (node (ref "LED74") (pin "4") (pinfunction "BLUE_C_4") (pintype "bidirectional"))
      (node (ref "LED74") (pin "5") (pinfunction "RED_C_5") (pintype "bidirectional"))
      (node (ref "LED74") (pin "6") (pinfunction "GREEN_C_6") (pintype "bidirectional"))
      (node (ref "LED75") (pin "1") (pinfunction "GREEN_A_1") (pintype "bidirectional"))
      (node (ref "LED75") (pin "2") (pinfunction "RED_A_2") (pintype "bidirectional"))
      (node (ref "LED75") (pin "3") (pinfunction "BLUE_A_3") (pintype "bidirectional"))
    )
    (net (code "72") (name "Net-(LED76-BLUE_C)") (class "Default")
      (node (ref "LED76") (pin "4") (pinfunction "BLUE_C_4") (pintype "bidirectional"))
      (node (ref "LED76") (pin "5") (pinfunction "RED_C_5") (pintype "bidirectional"))
      (node (ref "LED76") (pin "6") (pinfunction "GREEN_C_6") (pintype "bidirectional"))
      (node (ref "LED77") (pin "1") (pinfunction "GREEN_A_1") (pintype "bidirectional"))
      (node (ref "LED77") (pin "2") (pinfunction "RED_A_2") (pintype "bidirectional"))
      (node (ref "LED77") (pin "3") (pinfunction "BLUE_A_3") (pintype "bidirectional"))
    )
    (net (code "73") (name "Net-(LED77-BLUE_C)") (class "Default")
      (node (ref "LED77") (pin "4") (pinfunction "BLUE_C_4") (pintype "bidirectional"))
      (node (ref "LED77") (pin "5") (pinfunction "RED_C_5") (pintype "bidirectional"))
      (node (ref "LED77") (pin "6") (pinfunction "GREEN_C_6") (pintype "bidirectional"))
      (node (ref "LED78") (pin "1") (pinfunction "GREEN_A_1") (pintype "bidirectional"))
      (node (ref "LED78") (pin "2") (pinfunction "RED_A_2") (pintype "bidirectional"))
      (node (ref "LED78") (pin "3") (pinfunction "BLUE_A_3") (pintype "bidirectional"))
    )
    (net (code "74") (name "Net-(LED79-BLUE_C)") (class "Default")
      (node (ref "LED79") (pin "4") (pinfunction "BLUE_C_4") (pintype "bidirectional"))
      (node (ref "LED79") (pin "5") (pinfunction "RED_C_5") (pintype "bidirectional"))
      (node (ref "LED79") (pin "6") (pinfunction "GREEN_C_6") (pintype "bidirectional"))
      (node (ref "LED80") (pin "1") (pinfunction "GREEN_A_1") (pintype "bidirectional"))
      (node (ref "LED80") (pin "2") (pinfunction "RED_A_2") (pintype "bidirectional"))
      (node (ref "LED80") (pin "3") (pinfunction "BLUE_A_3") (pintype "bidirectional"))
    )
    (net (code "75") (name "Net-(LED80-BLUE_C)") (class "Default")
      (node (ref "LED80") (pin "4") (pinfunction "BLUE_C_4") (pintype "bidirectional"))
      (node (ref "LED80") (pin "5") (pinfunction "RED_C_5") (pintype "bidirectional"))
      (node (ref "LED80") (pin "6") (pinfunction "GREEN_C_6") (pintype "bidirectional"))
      (node (ref "LED81") (pin "1") (pinfunction "GREEN_A_1") (pintype "bidirectional"))
      (node (ref "LED81") (pin "2") (pinfunction "RED_A_2") (pintype "bidirectional"))
      (node (ref "LED81") (pin "3") (pinfunction "BLUE_A_3") (pintype "bidirectional"))
    )
    (net (code "76") (name "Net-(LED82-BLUE_C)") (class "Default")
      (node (ref "LED82") (pin "4") (pinfunction "BLUE_C_4") (pintype "bidirectional"))
      (node (ref "LED82") (pin "5") (pinfunction "RED_C_5") (pintype "bidirectional"))
      (node (ref "LED82") (pin "6") (pinfunction "GREEN_C_6") (pintype "bidirectional"))
      (node (ref "LED83") (pin "1") (pinfunction "GREEN_A_1") (pintype "bidirectional"))
      (node (ref "LED83") (pin "2") (pinfunction "RED_A_2") (pintype "bidirectional"))
      (node (ref "LED83") (pin "3") (pinfunction "BLUE_A_3") (pintype "bidirectional"))
    )
    (net (code "77") (name "Net-(LED83-BLUE_C)") (class "Default")
      (node (ref "LED83") (pin "4") (pinfunction "BLUE_C_4") (pintype "bidirectional"))
      (node (ref "LED83") (pin "5") (pinfunction "RED_C_5") (pintype "bidirectional"))
      (node (ref "LED83") (pin "6") (pinfunction "GREEN_C_6") (pintype "bidirectional"))
      (node (ref "LED84") (pin "1") (pinfunction "GREEN_A_1") (pintype "bidirectional"))
      (node (ref "LED84") (pin "2") (pinfunction "RED_A_2") (pintype "bidirectional"))
      (node (ref "LED84") (pin "3") (pinfunction "BLUE_A_3") (pintype "bidirectional"))
    )
    (net (code "78") (name "Net-(M1-D)") (class "Default")
      (node (ref "D10") (pin "A") (pinfunction "A_A") (pintype "passive"))
      (node (ref "M1") (pin "3") (pinfunction "D_3") (pintype "passive"))
    )
    (net (code "79") (name "Net-(M1-G)") (class "Default")
      (node (ref "M1") (pin "1") (pinfunction "G_1") (pintype "passive"))
      (node (ref "R11") (pin "2") (pinfunction "2_2") (pintype "passive"))
      (node (ref "R15") (pin "1") (pinfunction "1_1") (pintype "passive"))
    )
    (net (code "80") (name "Net-(U$2-CH_PD)") (class "Default")
      (node (ref "R28") (pin "2") (pinfunction "2_2") (pintype "passive"))
      (node (ref "U$2") (pin "11") (pinfunction "CH_PD_11") (pintype "bidirectional"))
    )
    (net (code "81") (name "Net-(U$4-XI)") (class "Default")
      (node (ref "12MHZ") (pin "1") (pinfunction "1_1") (pintype "passive"))
      (node (ref "C12") (pin "2") (pinfunction "2_2") (pintype "passive"))
      (node (ref "U$4") (pin "7") (pinfunction "XI_7") (pintype "bidirectional"))
    )
    (net (code "82") (name "Net-(U$4-XO)") (class "Default")
      (node (ref "12MHZ") (pin "2") (pinfunction "2_2") (pintype "passive"))
      (node (ref "C10") (pin "2") (pinfunction "2_2") (pintype "passive"))
      (node (ref "U$4") (pin "8") (pinfunction "XO_8") (pintype "bidirectional"))
    )
    (net (code "83") (name "unconnected-(LED1-BLUE_A-Pad3)") (class "Default")
      (node (ref "LED1") (pin "3") (pinfunction "BLUE_A_3") (pintype "bidirectional"))
    )
    (net (code "84") (name "unconnected-(LED1-GREEN_A-Pad1)") (class "Default")
      (node (ref "LED1") (pin "1") (pinfunction "GREEN_A_1") (pintype "bidirectional"))
    )
    (net (code "85") (name "unconnected-(LED1-RED_A-Pad2)") (class "Default")
      (node (ref "LED1") (pin "2") (pinfunction "RED_A_2") (pintype "bidirectional"))
    )
    (net (code "86") (name "unconnected-(LED3-BLUE_C-Pad4)") (class "Default")
      (node (ref "LED3") (pin "4") (pinfunction "BLUE_C_4") (pintype "bidirectional"))
    )
    (net (code "87") (name "unconnected-(LED3-GREEN_C-Pad6)") (class "Default")
      (node (ref "LED3") (pin "6") (pinfunction "GREEN_C_6") (pintype "bidirectional"))
    )
    (net (code "88") (name "unconnected-(LED3-RED_C-Pad5)") (class "Default")
      (node (ref "LED3") (pin "5") (pinfunction "RED_C_5") (pintype "bidirectional"))
    )
    (net (code "89") (name "unconnected-(LED4-BLUE_A-Pad3)") (class "Default")
      (node (ref "LED4") (pin "3") (pinfunction "BLUE_A_3") (pintype "bidirectional"))
    )
    (net (code "90") (name "unconnected-(LED4-GREEN_A-Pad1)") (class "Default")
      (node (ref "LED4") (pin "1") (pinfunction "GREEN_A_1") (pintype "bidirectional"))
    )
    (net (code "91") (name "unconnected-(LED4-RED_A-Pad2)") (class "Default")
      (node (ref "LED4") (pin "2") (pinfunction "RED_A_2") (pintype "bidirectional"))
    )
    (net (code "92") (name "unconnected-(LED6-BLUE_C-Pad4)") (class "Default")
      (node (ref "LED6") (pin "4") (pinfunction "BLUE_C_4") (pintype "bidirectional"))
    )
    (net (code "93") (name "unconnected-(LED6-GREEN_C-Pad6)") (class "Default")
      (node (ref "LED6") (pin "6") (pinfunction "GREEN_C_6") (pintype "bidirectional"))
    )
    (net (code "94") (name "unconnected-(LED6-RED_C-Pad5)") (class "Default")
      (node (ref "LED6") (pin "5") (pinfunction "RED_C_5") (pintype "bidirectional"))
    )
    (net (code "95") (name "unconnected-(LED7-BLUE_A-Pad3)") (class "Default")
      (node (ref "LED7") (pin "3") (pinfunction "BLUE_A_3") (pintype "bidirectional"))
    )
    (net (code "96") (name "unconnected-(LED7-GREEN_A-Pad1)") (class "Default")
      (node (ref "LED7") (pin "1") (pinfunction "GREEN_A_1") (pintype "bidirectional"))
    )
    (net (code "97") (name "unconnected-(LED7-RED_A-Pad2)") (class "Default")
      (node (ref "LED7") (pin "2") (pinfunction "RED_A_2") (pintype "bidirectional"))
    )
    (net (code "98") (name "unconnected-(LED9-BLUE_C-Pad4)") (class "Default")
      (node (ref "LED9") (pin "4") (pinfunction "BLUE_C_4") (pintype "bidirectional"))
    )
    (net (code "99") (name "unconnected-(LED9-GREEN_C-Pad6)") (class "Default")
      (node (ref "LED9") (pin "6") (pinfunction "GREEN_C_6") (pintype "bidirectional"))
    )
    (net (code "100") (name "unconnected-(LED9-RED_C-Pad5)") (class "Default")
      (node (ref "LED9") (pin "5") (pinfunction "RED_C_5") (pintype "bidirectional"))
    )
    (net (code "101") (name "unconnected-(LED10-BLUE_A-Pad3)") (class "Default")
      (node (ref "LED10") (pin "3") (pinfunction "BLUE_A_3") (pintype "bidirectional"))
    )
    (net (code "102") (name "unconnected-(LED10-GREEN_A-Pad1)") (class "Default")
      (node (ref "LED10") (pin "1") (pinfunction "GREEN_A_1") (pintype "bidirectional"))
    )
    (net (code "103") (name "unconnected-(LED10-RED_A-Pad2)") (class "Default")
      (node (ref "LED10") (pin "2") (pinfunction "RED_A_2") (pintype "bidirectional"))
    )
    (net (code "104") (name "unconnected-(LED12-BLUE_C-Pad4)") (class "Default")
      (node (ref "LED12") (pin "4") (pinfunction "BLUE_C_4") (pintype "bidirectional"))
    )
    (net (code "105") (name "unconnected-(LED12-GREEN_C-Pad6)") (class "Default")
      (node (ref "LED12") (pin "6") (pinfunction "GREEN_C_6") (pintype "bidirectional"))
    )
    (net (code "106") (name "unconnected-(LED12-RED_C-Pad5)") (class "Default")
      (node (ref "LED12") (pin "5") (pinfunction "RED_C_5") (pintype "bidirectional"))
    )
    (net (code "107") (name "unconnected-(LED13-BLUE_A-Pad3)") (class "Default")
      (node (ref "LED13") (pin "3") (pinfunction "BLUE_A_3") (pintype "bidirectional"))
    )
    (net (code "108") (name "unconnected-(LED13-GREEN_A-Pad1)") (class "Default")
      (node (ref "LED13") (pin "1") (pinfunction "GREEN_A_1") (pintype "bidirectional"))
    )
    (net (code "109") (name "unconnected-(LED13-RED_A-Pad2)") (class "Default")
      (node (ref "LED13") (pin "2") (pinfunction "RED_A_2") (pintype "bidirectional"))
    )
    (net (code "110") (name "unconnected-(LED15-BLUE_C-Pad4)") (class "Default")
      (node (ref "LED15") (pin "4") (pinfunction "BLUE_C_4") (pintype "bidirectional"))
    )
    (net (code "111") (name "unconnected-(LED15-GREEN_C-Pad6)") (class "Default")
      (node (ref "LED15") (pin "6") (pinfunction "GREEN_C_6") (pintype "bidirectional"))
    )
    (net (code "112") (name "unconnected-(LED15-RED_C-Pad5)") (class "Default")
      (node (ref "LED15") (pin "5") (pinfunction "RED_C_5") (pintype "bidirectional"))
    )
    (net (code "113") (name "unconnected-(LED16-BLUE_A-Pad3)") (class "Default")
      (node (ref "LED16") (pin "3") (pinfunction "BLUE_A_3") (pintype "bidirectional"))
    )
    (net (code "114") (name "unconnected-(LED16-GREEN_A-Pad1)") (class "Default")
      (node (ref "LED16") (pin "1") (pinfunction "GREEN_A_1") (pintype "bidirectional"))
    )
    (net (code "115") (name "unconnected-(LED16-RED_A-Pad2)") (class "Default")
      (node (ref "LED16") (pin "2") (pinfunction "RED_A_2") (pintype "bidirectional"))
    )
    (net (code "116") (name "unconnected-(LED18-BLUE_C-Pad4)") (class "Default")
      (node (ref "LED18") (pin "4") (pinfunction "BLUE_C_4") (pintype "bidirectional"))
    )
    (net (code "117") (name "unconnected-(LED18-GREEN_C-Pad6)") (class "Default")
      (node (ref "LED18") (pin "6") (pinfunction "GREEN_C_6") (pintype "bidirectional"))
    )
    (net (code "118") (name "unconnected-(LED18-RED_C-Pad5)") (class "Default")
      (node (ref "LED18") (pin "5") (pinfunction "RED_C_5") (pintype "bidirectional"))
    )
    (net (code "119") (name "unconnected-(LED19-BLUE_A-Pad3)") (class "Default")
      (node (ref "LED19") (pin "3") (pinfunction "BLUE_A_3") (pintype "bidirectional"))
    )
    (net (code "120") (name "unconnected-(LED19-GREEN_A-Pad1)") (class "Default")
      (node (ref "LED19") (pin "1") (pinfunction "GREEN_A_1") (pintype "bidirectional"))
    )
    (net (code "121") (name "unconnected-(LED19-RED_A-Pad2)") (class "Default")
      (node (ref "LED19") (pin "2") (pinfunction "RED_A_2") (pintype "bidirectional"))
    )
    (net (code "122") (name "unconnected-(LED21-BLUE_C-Pad4)") (class "Default")
      (node (ref "LED21") (pin "4") (pinfunction "BLUE_C_4") (pintype "bidirectional"))
    )
    (net (code "123") (name "unconnected-(LED21-GREEN_C-Pad6)") (class "Default")
      (node (ref "LED21") (pin "6") (pinfunction "GREEN_C_6") (pintype "bidirectional"))
    )
    (net (code "124") (name "unconnected-(LED21-RED_C-Pad5)") (class "Default")
      (node (ref "LED21") (pin "5") (pinfunction "RED_C_5") (pintype "bidirectional"))
    )
    (net (code "125") (name "unconnected-(LED22-BLUE_A-Pad3)") (class "Default")
      (node (ref "LED22") (pin "3") (pinfunction "BLUE_A_3") (pintype "bidirectional"))
    )
    (net (code "126") (name "unconnected-(LED22-GREEN_A-Pad1)") (class "Default")
      (node (ref "LED22") (pin "1") (pinfunction "GREEN_A_1") (pintype "bidirectional"))
    )
    (net (code "127") (name "unconnected-(LED22-RED_A-Pad2)") (class "Default")
      (node (ref "LED22") (pin "2") (pinfunction "RED_A_2") (pintype "bidirectional"))
    )
    (net (code "128") (name "unconnected-(LED24-BLUE_C-Pad4)") (class "Default")
      (node (ref "LED24") (pin "4") (pinfunction "BLUE_C_4") (pintype "bidirectional"))
    )
    (net (code "129") (name "unconnected-(LED24-GREEN_C-Pad6)") (class "Default")
      (node (ref "LED24") (pin "6") (pinfunction "GREEN_C_6") (pintype "bidirectional"))
    )
    (net (code "130") (name "unconnected-(LED24-RED_C-Pad5)") (class "Default")
      (node (ref "LED24") (pin "5") (pinfunction "RED_C_5") (pintype "bidirectional"))
    )
    (net (code "131") (name "unconnected-(LED25-BLUE_A-Pad3)") (class "Default")
      (node (ref "LED25") (pin "3") (pinfunction "BLUE_A_3") (pintype "bidirectional"))
    )
    (net (code "132") (name "unconnected-(LED25-GREEN_A-Pad1)") (class "Default")
      (node (ref "LED25") (pin "1") (pinfunction "GREEN_A_1") (pintype "bidirectional"))
    )
    (net (code "133") (name "unconnected-(LED25-RED_A-Pad2)") (class "Default")
      (node (ref "LED25") (pin "2") (pinfunction "RED_A_2") (pintype "bidirectional"))
    )
    (net (code "134") (name "unconnected-(LED27-BLUE_C-Pad4)") (class "Default")
      (node (ref "LED27") (pin "4") (pinfunction "BLUE_C_4") (pintype "bidirectional"))
    )
    (net (code "135") (name "unconnected-(LED27-GREEN_C-Pad6)") (class "Default")
      (node (ref "LED27") (pin "6") (pinfunction "GREEN_C_6") (pintype "bidirectional"))
    )
    (net (code "136") (name "unconnected-(LED27-RED_C-Pad5)") (class "Default")
      (node (ref "LED27") (pin "5") (pinfunction "RED_C_5") (pintype "bidirectional"))
    )
    (net (code "137") (name "unconnected-(LED28-BLUE_A-Pad3)") (class "Default")
      (node (ref "LED28") (pin "3") (pinfunction "BLUE_A_3") (pintype "bidirectional"))
    )
    (net (code "138") (name "unconnected-(LED28-GREEN_A-Pad1)") (class "Default")
      (node (ref "LED28") (pin "1") (pinfunction "GREEN_A_1") (pintype "bidirectional"))
    )
    (net (code "139") (name "unconnected-(LED28-RED_A-Pad2)") (class "Default")
      (node (ref "LED28") (pin "2") (pinfunction "RED_A_2") (pintype "bidirectional"))
    )
    (net (code "140") (name "unconnected-(LED30-BLUE_C-Pad4)") (class "Default")
      (node (ref "LED30") (pin "4") (pinfunction "BLUE_C_4") (pintype "bidirectional"))
    )
    (net (code "141") (name "unconnected-(LED30-GREEN_C-Pad6)") (class "Default")
      (node (ref "LED30") (pin "6") (pinfunction "GREEN_C_6") (pintype "bidirectional"))
    )
    (net (code "142") (name "unconnected-(LED30-RED_C-Pad5)") (class "Default")
      (node (ref "LED30") (pin "5") (pinfunction "RED_C_5") (pintype "bidirectional"))
    )
    (net (code "143") (name "unconnected-(LED31-BLUE_A-Pad3)") (class "Default")
      (node (ref "LED31") (pin "3") (pinfunction "BLUE_A_3") (pintype "bidirectional"))
    )
    (net (code "144") (name "unconnected-(LED31-GREEN_A-Pad1)") (class "Default")
      (node (ref "LED31") (pin "1") (pinfunction "GREEN_A_1") (pintype "bidirectional"))
    )
    (net (code "145") (name "unconnected-(LED31-RED_A-Pad2)") (class "Default")
      (node (ref "LED31") (pin "2") (pinfunction "RED_A_2") (pintype "bidirectional"))
    )
    (net (code "146") (name "unconnected-(LED33-BLUE_C-Pad4)") (class "Default")
      (node (ref "LED33") (pin "4") (pinfunction "BLUE_C_4") (pintype "bidirectional"))
    )
    (net (code "147") (name "unconnected-(LED33-GREEN_C-Pad6)") (class "Default")
      (node (ref "LED33") (pin "6") (pinfunction "GREEN_C_6") (pintype "bidirectional"))
    )
    (net (code "148") (name "unconnected-(LED33-RED_C-Pad5)") (class "Default")
      (node (ref "LED33") (pin "5") (pinfunction "RED_C_5") (pintype "bidirectional"))
    )
    (net (code "149") (name "unconnected-(LED34-BLUE_A-Pad3)") (class "Default")
      (node (ref "LED34") (pin "3") (pinfunction "BLUE_A_3") (pintype "bidirectional"))
    )
    (net (code "150") (name "unconnected-(LED34-GREEN_A-Pad1)") (class "Default")
      (node (ref "LED34") (pin "1") (pinfunction "GREEN_A_1") (pintype "bidirectional"))
    )
    (net (code "151") (name "unconnected-(LED34-RED_A-Pad2)") (class "Default")
      (node (ref "LED34") (pin "2") (pinfunction "RED_A_2") (pintype "bidirectional"))
    )
    (net (code "152") (name "unconnected-(LED36-BLUE_C-Pad4)") (class "Default")
      (node (ref "LED36") (pin "4") (pinfunction "BLUE_C_4") (pintype "bidirectional"))
    )
    (net (code "153") (name "unconnected-(LED36-GREEN_C-Pad6)") (class "Default")
      (node (ref "LED36") (pin "6") (pinfunction "GREEN_C_6") (pintype "bidirectional"))
    )
    (net (code "154") (name "unconnected-(LED36-RED_C-Pad5)") (class "Default")
      (node (ref "LED36") (pin "5") (pinfunction "RED_C_5") (pintype "bidirectional"))
    )
    (net (code "155") (name "unconnected-(LED37-BLUE_A-Pad3)") (class "Default")
      (node (ref "LED37") (pin "3") (pinfunction "BLUE_A_3") (pintype "bidirectional"))
    )
    (net (code "156") (name "unconnected-(LED37-GREEN_A-Pad1)") (class "Default")
      (node (ref "LED37") (pin "1") (pinfunction "GREEN_A_1") (pintype "bidirectional"))
    )
    (net (code "157") (name "unconnected-(LED37-RED_A-Pad2)") (class "Default")
      (node (ref "LED37") (pin "2") (pinfunction "RED_A_2") (pintype "bidirectional"))
    )
    (net (code "158") (name "unconnected-(LED39-BLUE_C-Pad4)") (class "Default")
      (node (ref "LED39") (pin "4") (pinfunction "BLUE_C_4") (pintype "bidirectional"))
    )
    (net (code "159") (name "unconnected-(LED39-GREEN_C-Pad6)") (class "Default")
      (node (ref "LED39") (pin "6") (pinfunction "GREEN_C_6") (pintype "bidirectional"))
    )
    (net (code "160") (name "unconnected-(LED39-RED_C-Pad5)") (class "Default")
      (node (ref "LED39") (pin "5") (pinfunction "RED_C_5") (pintype "bidirectional"))
    )
    (net (code "161") (name "unconnected-(LED40-BLUE_A-Pad3)") (class "Default")
      (node (ref "LED40") (pin "3") (pinfunction "BLUE_A_3") (pintype "bidirectional"))
    )
    (net (code "162") (name "unconnected-(LED40-GREEN_A-Pad1)") (class "Default")
      (node (ref "LED40") (pin "1") (pinfunction "GREEN_A_1") (pintype "bidirectional"))
    )
    (net (code "163") (name "unconnected-(LED40-RED_A-Pad2)") (class "Default")
      (node (ref "LED40") (pin "2") (pinfunction "RED_A_2") (pintype "bidirectional"))
    )
    (net (code "164") (name "unconnected-(LED42-BLUE_C-Pad4)") (class "Default")
      (node (ref "LED42") (pin "4") (pinfunction "BLUE_C_4") (pintype "bidirectional"))
    )
    (net (code "165") (name "unconnected-(LED42-GREEN_C-Pad6)") (class "Default")
      (node (ref "LED42") (pin "6") (pinfunction "GREEN_C_6") (pintype "bidirectional"))
    )
    (net (code "166") (name "unconnected-(LED42-RED_C-Pad5)") (class "Default")
      (node (ref "LED42") (pin "5") (pinfunction "RED_C_5") (pintype "bidirectional"))
    )
    (net (code "167") (name "unconnected-(LED43-BLUE_A-Pad3)") (class "Default")
      (node (ref "LED43") (pin "3") (pinfunction "BLUE_A_3") (pintype "bidirectional"))
    )
    (net (code "168") (name "unconnected-(LED43-GREEN_A-Pad1)") (class "Default")
      (node (ref "LED43") (pin "1") (pinfunction "GREEN_A_1") (pintype "bidirectional"))
    )
    (net (code "169") (name "unconnected-(LED43-RED_A-Pad2)") (class "Default")
      (node (ref "LED43") (pin "2") (pinfunction "RED_A_2") (pintype "bidirectional"))
    )
    (net (code "170") (name "unconnected-(LED45-BLUE_C-Pad4)") (class "Default")
      (node (ref "LED45") (pin "4") (pinfunction "BLUE_C_4") (pintype "bidirectional"))
    )
    (net (code "171") (name "unconnected-(LED45-GREEN_C-Pad6)") (class "Default")
      (node (ref "LED45") (pin "6") (pinfunction "GREEN_C_6") (pintype "bidirectional"))
    )
    (net (code "172") (name "unconnected-(LED45-RED_C-Pad5)") (class "Default")
      (node (ref "LED45") (pin "5") (pinfunction "RED_C_5") (pintype "bidirectional"))
    )
    (net (code "173") (name "unconnected-(LED46-BLUE_A-Pad3)") (class "Default")
      (node (ref "LED46") (pin "3") (pinfunction "BLUE_A_3") (pintype "bidirectional"))
    )
    (net (code "174") (name "unconnected-(LED46-GREEN_A-Pad1)") (class "Default")
      (node (ref "LED46") (pin "1") (pinfunction "GREEN_A_1") (pintype "bidirectional"))
    )
    (net (code "175") (name "unconnected-(LED46-RED_A-Pad2)") (class "Default")
      (node (ref "LED46") (pin "2") (pinfunction "RED_A_2") (pintype "bidirectional"))
    )
    (net (code "176") (name "unconnected-(LED48-BLUE_C-Pad4)") (class "Default")
      (node (ref "LED48") (pin "4") (pinfunction "BLUE_C_4") (pintype "bidirectional"))
    )
    (net (code "177") (name "unconnected-(LED48-GREEN_C-Pad6)") (class "Default")
      (node (ref "LED48") (pin "6") (pinfunction "GREEN_C_6") (pintype "bidirectional"))
    )
    (net (code "178") (name "unconnected-(LED48-RED_C-Pad5)") (class "Default")
      (node (ref "LED48") (pin "5") (pinfunction "RED_C_5") (pintype "bidirectional"))
    )
    (net (code "179") (name "unconnected-(LED49-BLUE_A-Pad3)") (class "Default")
      (node (ref "LED49") (pin "3") (pinfunction "BLUE_A_3") (pintype "bidirectional"))
    )
    (net (code "180") (name "unconnected-(LED49-GREEN_A-Pad1)") (class "Default")
      (node (ref "LED49") (pin "1") (pinfunction "GREEN_A_1") (pintype "bidirectional"))
    )
    (net (code "181") (name "unconnected-(LED49-RED_A-Pad2)") (class "Default")
      (node (ref "LED49") (pin "2") (pinfunction "RED_A_2") (pintype "bidirectional"))
    )
    (net (code "182") (name "unconnected-(LED51-BLUE_C-Pad4)") (class "Default")
      (node (ref "LED51") (pin "4") (pinfunction "BLUE_C_4") (pintype "bidirectional"))
    )
    (net (code "183") (name "unconnected-(LED51-GREEN_C-Pad6)") (class "Default")
      (node (ref "LED51") (pin "6") (pinfunction "GREEN_C_6") (pintype "bidirectional"))
    )
    (net (code "184") (name "unconnected-(LED51-RED_C-Pad5)") (class "Default")
      (node (ref "LED51") (pin "5") (pinfunction "RED_C_5") (pintype "bidirectional"))
    )
    (net (code "185") (name "unconnected-(LED52-BLUE_A-Pad3)") (class "Default")
      (node (ref "LED52") (pin "3") (pinfunction "BLUE_A_3") (pintype "bidirectional"))
    )
    (net (code "186") (name "unconnected-(LED52-GREEN_A-Pad1)") (class "Default")
      (node (ref "LED52") (pin "1") (pinfunction "GREEN_A_1") (pintype "bidirectional"))
    )
    (net (code "187") (name "unconnected-(LED52-RED_A-Pad2)") (class "Default")
      (node (ref "LED52") (pin "2") (pinfunction "RED_A_2") (pintype "bidirectional"))
    )
    (net (code "188") (name "unconnected-(LED54-BLUE_C-Pad4)") (class "Default")
      (node (ref "LED54") (pin "4") (pinfunction "BLUE_C_4") (pintype "bidirectional"))
    )
    (net (code "189") (name "unconnected-(LED54-GREEN_C-Pad6)") (class "Default")
      (node (ref "LED54") (pin "6") (pinfunction "GREEN_C_6") (pintype "bidirectional"))
    )
    (net (code "190") (name "unconnected-(LED54-RED_C-Pad5)") (class "Default")
      (node (ref "LED54") (pin "5") (pinfunction "RED_C_5") (pintype "bidirectional"))
    )
    (net (code "191") (name "unconnected-(LED55-BLUE_A-Pad3)") (class "Default")
      (node (ref "LED55") (pin "3") (pinfunction "BLUE_A_3") (pintype "bidirectional"))
    )
    (net (code "192") (name "unconnected-(LED55-GREEN_A-Pad1)") (class "Default")
      (node (ref "LED55") (pin "1") (pinfunction "GREEN_A_1") (pintype "bidirectional"))
    )
    (net (code "193") (name "unconnected-(LED55-RED_A-Pad2)") (class "Default")
      (node (ref "LED55") (pin "2") (pinfunction "RED_A_2") (pintype "bidirectional"))
    )
    (net (code "194") (name "unconnected-(LED57-BLUE_C-Pad4)") (class "Default")
      (node (ref "LED57") (pin "4") (pinfunction "BLUE_C_4") (pintype "bidirectional"))
    )
    (net (code "195") (name "unconnected-(LED57-GREEN_C-Pad6)") (class "Default")
      (node (ref "LED57") (pin "6") (pinfunction "GREEN_C_6") (pintype "bidirectional"))
    )
    (net (code "196") (name "unconnected-(LED57-RED_C-Pad5)") (class "Default")
      (node (ref "LED57") (pin "5") (pinfunction "RED_C_5") (pintype "bidirectional"))
    )
    (net (code "197") (name "unconnected-(LED58-BLUE_A-Pad3)") (class "Default")
      (node (ref "LED58") (pin "3") (pinfunction "BLUE_A_3") (pintype "bidirectional"))
    )
    (net (code "198") (name "unconnected-(LED58-GREEN_A-Pad1)") (class "Default")
      (node (ref "LED58") (pin "1") (pinfunction "GREEN_A_1") (pintype "bidirectional"))
    )
    (net (code "199") (name "unconnected-(LED58-RED_A-Pad2)") (class "Default")
      (node (ref "LED58") (pin "2") (pinfunction "RED_A_2") (pintype "bidirectional"))
    )
    (net (code "200") (name "unconnected-(LED60-BLUE_C-Pad4)") (class "Default")
      (node (ref "LED60") (pin "4") (pinfunction "BLUE_C_4") (pintype "bidirectional"))
    )
    (net (code "201") (name "unconnected-(LED60-GREEN_C-Pad6)") (class "Default")
      (node (ref "LED60") (pin "6") (pinfunction "GREEN_C_6") (pintype "bidirectional"))
    )
    (net (code "202") (name "unconnected-(LED60-RED_C-Pad5)") (class "Default")
      (node (ref "LED60") (pin "5") (pinfunction "RED_C_5") (pintype "bidirectional"))
    )
    (net (code "203") (name "unconnected-(LED61-BLUE_A-Pad3)") (class "Default")
      (node (ref "LED61") (pin "3") (pinfunction "BLUE_A_3") (pintype "bidirectional"))
    )
    (net (code "204") (name "unconnected-(LED61-GREEN_A-Pad1)") (class "Default")
      (node (ref "LED61") (pin "1") (pinfunction "GREEN_A_1") (pintype "bidirectional"))
    )
    (net (code "205") (name "unconnected-(LED61-RED_A-Pad2)") (class "Default")
      (node (ref "LED61") (pin "2") (pinfunction "RED_A_2") (pintype "bidirectional"))
    )
    (net (code "206") (name "unconnected-(LED63-BLUE_C-Pad4)") (class "Default")
      (node (ref "LED63") (pin "4") (pinfunction "BLUE_C_4") (pintype "bidirectional"))
    )
    (net (code "207") (name "unconnected-(LED63-GREEN_C-Pad6)") (class "Default")
      (node (ref "LED63") (pin "6") (pinfunction "GREEN_C_6") (pintype "bidirectional"))
    )
    (net (code "208") (name "unconnected-(LED63-RED_C-Pad5)") (class "Default")
      (node (ref "LED63") (pin "5") (pinfunction "RED_C_5") (pintype "bidirectional"))
    )
    (net (code "209") (name "unconnected-(LED64-BLUE_A-Pad3)") (class "Default")
      (node (ref "LED64") (pin "3") (pinfunction "BLUE_A_3") (pintype "bidirectional"))
    )
    (net (code "210") (name "unconnected-(LED64-GREEN_A-Pad1)") (class "Default")
      (node (ref "LED64") (pin "1") (pinfunction "GREEN_A_1") (pintype "bidirectional"))
    )
    (net (code "211") (name "unconnected-(LED64-RED_A-Pad2)") (class "Default")
      (node (ref "LED64") (pin "2") (pinfunction "RED_A_2") (pintype "bidirectional"))
    )
    (net (code "212") (name "unconnected-(LED66-BLUE_C-Pad4)") (class "Default")
      (node (ref "LED66") (pin "4") (pinfunction "BLUE_C_4") (pintype "bidirectional"))
    )
    (net (code "213") (name "unconnected-(LED66-GREEN_C-Pad6)") (class "Default")
      (node (ref "LED66") (pin "6") (pinfunction "GREEN_C_6") (pintype "bidirectional"))
    )
    (net (code "214") (name "unconnected-(LED66-RED_C-Pad5)") (class "Default")
      (node (ref "LED66") (pin "5") (pinfunction "RED_C_5") (pintype "bidirectional"))
    )
    (net (code "215") (name "unconnected-(LED67-BLUE_A-Pad3)") (class "Default")
      (node (ref "LED67") (pin "3") (pinfunction "BLUE_A_3") (pintype "bidirectional"))
    )
    (net (code "216") (name "unconnected-(LED67-GREEN_A-Pad1)") (class "Default")
      (node (ref "LED67") (pin "1") (pinfunction "GREEN_A_1") (pintype "bidirectional"))
    )
    (net (code "217") (name "unconnected-(LED67-RED_A-Pad2)") (class "Default")
      (node (ref "LED67") (pin "2") (pinfunction "RED_A_2") (pintype "bidirectional"))
    )
    (net (code "218") (name "unconnected-(LED69-BLUE_C-Pad4)") (class "Default")
      (node (ref "LED69") (pin "4") (pinfunction "BLUE_C_4") (pintype "bidirectional"))
    )
    (net (code "219") (name "unconnected-(LED69-GREEN_C-Pad6)") (class "Default")
      (node (ref "LED69") (pin "6") (pinfunction "GREEN_C_6") (pintype "bidirectional"))
    )
    (net (code "220") (name "unconnected-(LED69-RED_C-Pad5)") (class "Default")
      (node (ref "LED69") (pin "5") (pinfunction "RED_C_5") (pintype "bidirectional"))
    )
    (net (code "221") (name "unconnected-(LED70-BLUE_A-Pad3)") (class "Default")
      (node (ref "LED70") (pin "3") (pinfunction "BLUE_A_3") (pintype "bidirectional"))
    )
    (net (code "222") (name "unconnected-(LED70-GREEN_A-Pad1)") (class "Default")
      (node (ref "LED70") (pin "1") (pinfunction "GREEN_A_1") (pintype "bidirectional"))
    )
    (net (code "223") (name "unconnected-(LED70-RED_A-Pad2)") (class "Default")
      (node (ref "LED70") (pin "2") (pinfunction "RED_A_2") (pintype "bidirectional"))
    )
    (net (code "224") (name "unconnected-(LED72-BLUE_C-Pad4)") (class "Default")
      (node (ref "LED72") (pin "4") (pinfunction "BLUE_C_4") (pintype "bidirectional"))
    )
    (net (code "225") (name "unconnected-(LED72-GREEN_C-Pad6)") (class "Default")
      (node (ref "LED72") (pin "6") (pinfunction "GREEN_C_6") (pintype "bidirectional"))
    )
    (net (code "226") (name "unconnected-(LED72-RED_C-Pad5)") (class "Default")
      (node (ref "LED72") (pin "5") (pinfunction "RED_C_5") (pintype "bidirectional"))
    )
    (net (code "227") (name "unconnected-(LED73-BLUE_A-Pad3)") (class "Default")
      (node (ref "LED73") (pin "3") (pinfunction "BLUE_A_3") (pintype "bidirectional"))
    )
    (net (code "228") (name "unconnected-(LED73-GREEN_A-Pad1)") (class "Default")
      (node (ref "LED73") (pin "1") (pinfunction "GREEN_A_1") (pintype "bidirectional"))
    )
    (net (code "229") (name "unconnected-(LED73-RED_A-Pad2)") (class "Default")
      (node (ref "LED73") (pin "2") (pinfunction "RED_A_2") (pintype "bidirectional"))
    )
    (net (code "230") (name "unconnected-(LED75-BLUE_C-Pad4)") (class "Default")
      (node (ref "LED75") (pin "4") (pinfunction "BLUE_C_4") (pintype "bidirectional"))
    )
    (net (code "231") (name "unconnected-(LED75-GREEN_C-Pad6)") (class "Default")
      (node (ref "LED75") (pin "6") (pinfunction "GREEN_C_6") (pintype "bidirectional"))
    )
    (net (code "232") (name "unconnected-(LED75-RED_C-Pad5)") (class "Default")
      (node (ref "LED75") (pin "5") (pinfunction "RED_C_5") (pintype "bidirectional"))
    )
    (net (code "233") (name "unconnected-(LED76-BLUE_A-Pad3)") (class "Default")
      (node (ref "LED76") (pin "3") (pinfunction "BLUE_A_3") (pintype "bidirectional"))
    )
    (net (code "234") (name "unconnected-(LED76-GREEN_A-Pad1)") (class "Default")
      (node (ref "LED76") (pin "1") (pinfunction "GREEN_A_1") (pintype "bidirectional"))
    )
    (net (code "235") (name "unconnected-(LED76-RED_A-Pad2)") (class "Default")
      (node (ref "LED76") (pin "2") (pinfunction "RED_A_2") (pintype "bidirectional"))
    )
    (net (code "236") (name "unconnected-(LED78-BLUE_C-Pad4)") (class "Default")
      (node (ref "LED78") (pin "4") (pinfunction "BLUE_C_4") (pintype "bidirectional"))
    )
    (net (code "237") (name "unconnected-(LED78-GREEN_C-Pad6)") (class "Default")
      (node (ref "LED78") (pin "6") (pinfunction "GREEN_C_6") (pintype "bidirectional"))
    )
    (net (code "238") (name "unconnected-(LED78-RED_C-Pad5)") (class "Default")
      (node (ref "LED78") (pin "5") (pinfunction "RED_C_5") (pintype "bidirectional"))
    )
    (net (code "239") (name "unconnected-(LED79-BLUE_A-Pad3)") (class "Default")
      (node (ref "LED79") (pin "3") (pinfunction "BLUE_A_3") (pintype "bidirectional"))
    )
    (net (code "240") (name "unconnected-(LED79-GREEN_A-Pad1)") (class "Default")
      (node (ref "LED79") (pin "1") (pinfunction "GREEN_A_1") (pintype "bidirectional"))
    )
    (net (code "241") (name "unconnected-(LED79-RED_A-Pad2)") (class "Default")
      (node (ref "LED79") (pin "2") (pinfunction "RED_A_2") (pintype "bidirectional"))
    )
    (net (code "242") (name "unconnected-(LED81-BLUE_C-Pad4)") (class "Default")
      (node (ref "LED81") (pin "4") (pinfunction "BLUE_C_4") (pintype "bidirectional"))
    )
    (net (code "243") (name "unconnected-(LED81-GREEN_C-Pad6)") (class "Default")
      (node (ref "LED81") (pin "6") (pinfunction "GREEN_C_6") (pintype "bidirectional"))
    )
    (net (code "244") (name "unconnected-(LED81-RED_C-Pad5)") (class "Default")
      (node (ref "LED81") (pin "5") (pinfunction "RED_C_5") (pintype "bidirectional"))
    )
    (net (code "245") (name "unconnected-(LED82-BLUE_A-Pad3)") (class "Default")
      (node (ref "LED82") (pin "3") (pinfunction "BLUE_A_3") (pintype "bidirectional"))
    )
    (net (code "246") (name "unconnected-(LED82-GREEN_A-Pad1)") (class "Default")
      (node (ref "LED82") (pin "1") (pinfunction "GREEN_A_1") (pintype "bidirectional"))
    )
    (net (code "247") (name "unconnected-(LED82-RED_A-Pad2)") (class "Default")
      (node (ref "LED82") (pin "2") (pinfunction "RED_A_2") (pintype "bidirectional"))
    )
    (net (code "248") (name "unconnected-(LED84-BLUE_C-Pad4)") (class "Default")
      (node (ref "LED84") (pin "4") (pinfunction "BLUE_C_4") (pintype "bidirectional"))
    )
    (net (code "249") (name "unconnected-(LED84-GREEN_C-Pad6)") (class "Default")
      (node (ref "LED84") (pin "6") (pinfunction "GREEN_C_6") (pintype "bidirectional"))
    )
    (net (code "250") (name "unconnected-(LED84-RED_C-Pad5)") (class "Default")
      (node (ref "LED84") (pin "5") (pinfunction "RED_C_5") (pintype "bidirectional"))
    )
    (net (code "251") (name "unconnected-(U$4-CTS-Pad9)") (class "Default")
      (node (ref "U$4") (pin "9") (pinfunction "CTS_9") (pintype "bidirectional"))
    )
    (net (code "252") (name "unconnected-(U$4-DCD-Pad12)") (class "Default")
      (node (ref "U$4") (pin "12") (pinfunction "DCD_12") (pintype "bidirectional"))
    )
    (net (code "253") (name "unconnected-(U$4-DSR-Pad10)") (class "Default")
      (node (ref "U$4") (pin "10") (pinfunction "DSR_10") (pintype "bidirectional"))
    )
    (net (code "254") (name "unconnected-(U$4-DTR-Pad13)") (class "Default")
      (node (ref "U$4") (pin "13") (pinfunction "DTR_13") (pintype "bidirectional"))
    )
    (net (code "255") (name "unconnected-(U$4-RI-Pad11)") (class "Default")
      (node (ref "U$4") (pin "11") (pinfunction "RI_11") (pintype "bidirectional"))
    )
    (net (code "256") (name "unconnected-(U$4-RS232-Pad15)") (class "Default")
      (node (ref "U$4") (pin "15") (pinfunction "RS232_15") (pintype "bidirectional"))
    )
    (net (code "257") (name "unconnected-(U$4-RTS-Pad14)") (class "Default")
      (node (ref "U$4") (pin "14") (pinfunction "RTS_14") (pintype "bidirectional"))
    )
  )
)
